# Bidirectional_Amp.net
KiCad netlist of a schematic drawn in EAGLE
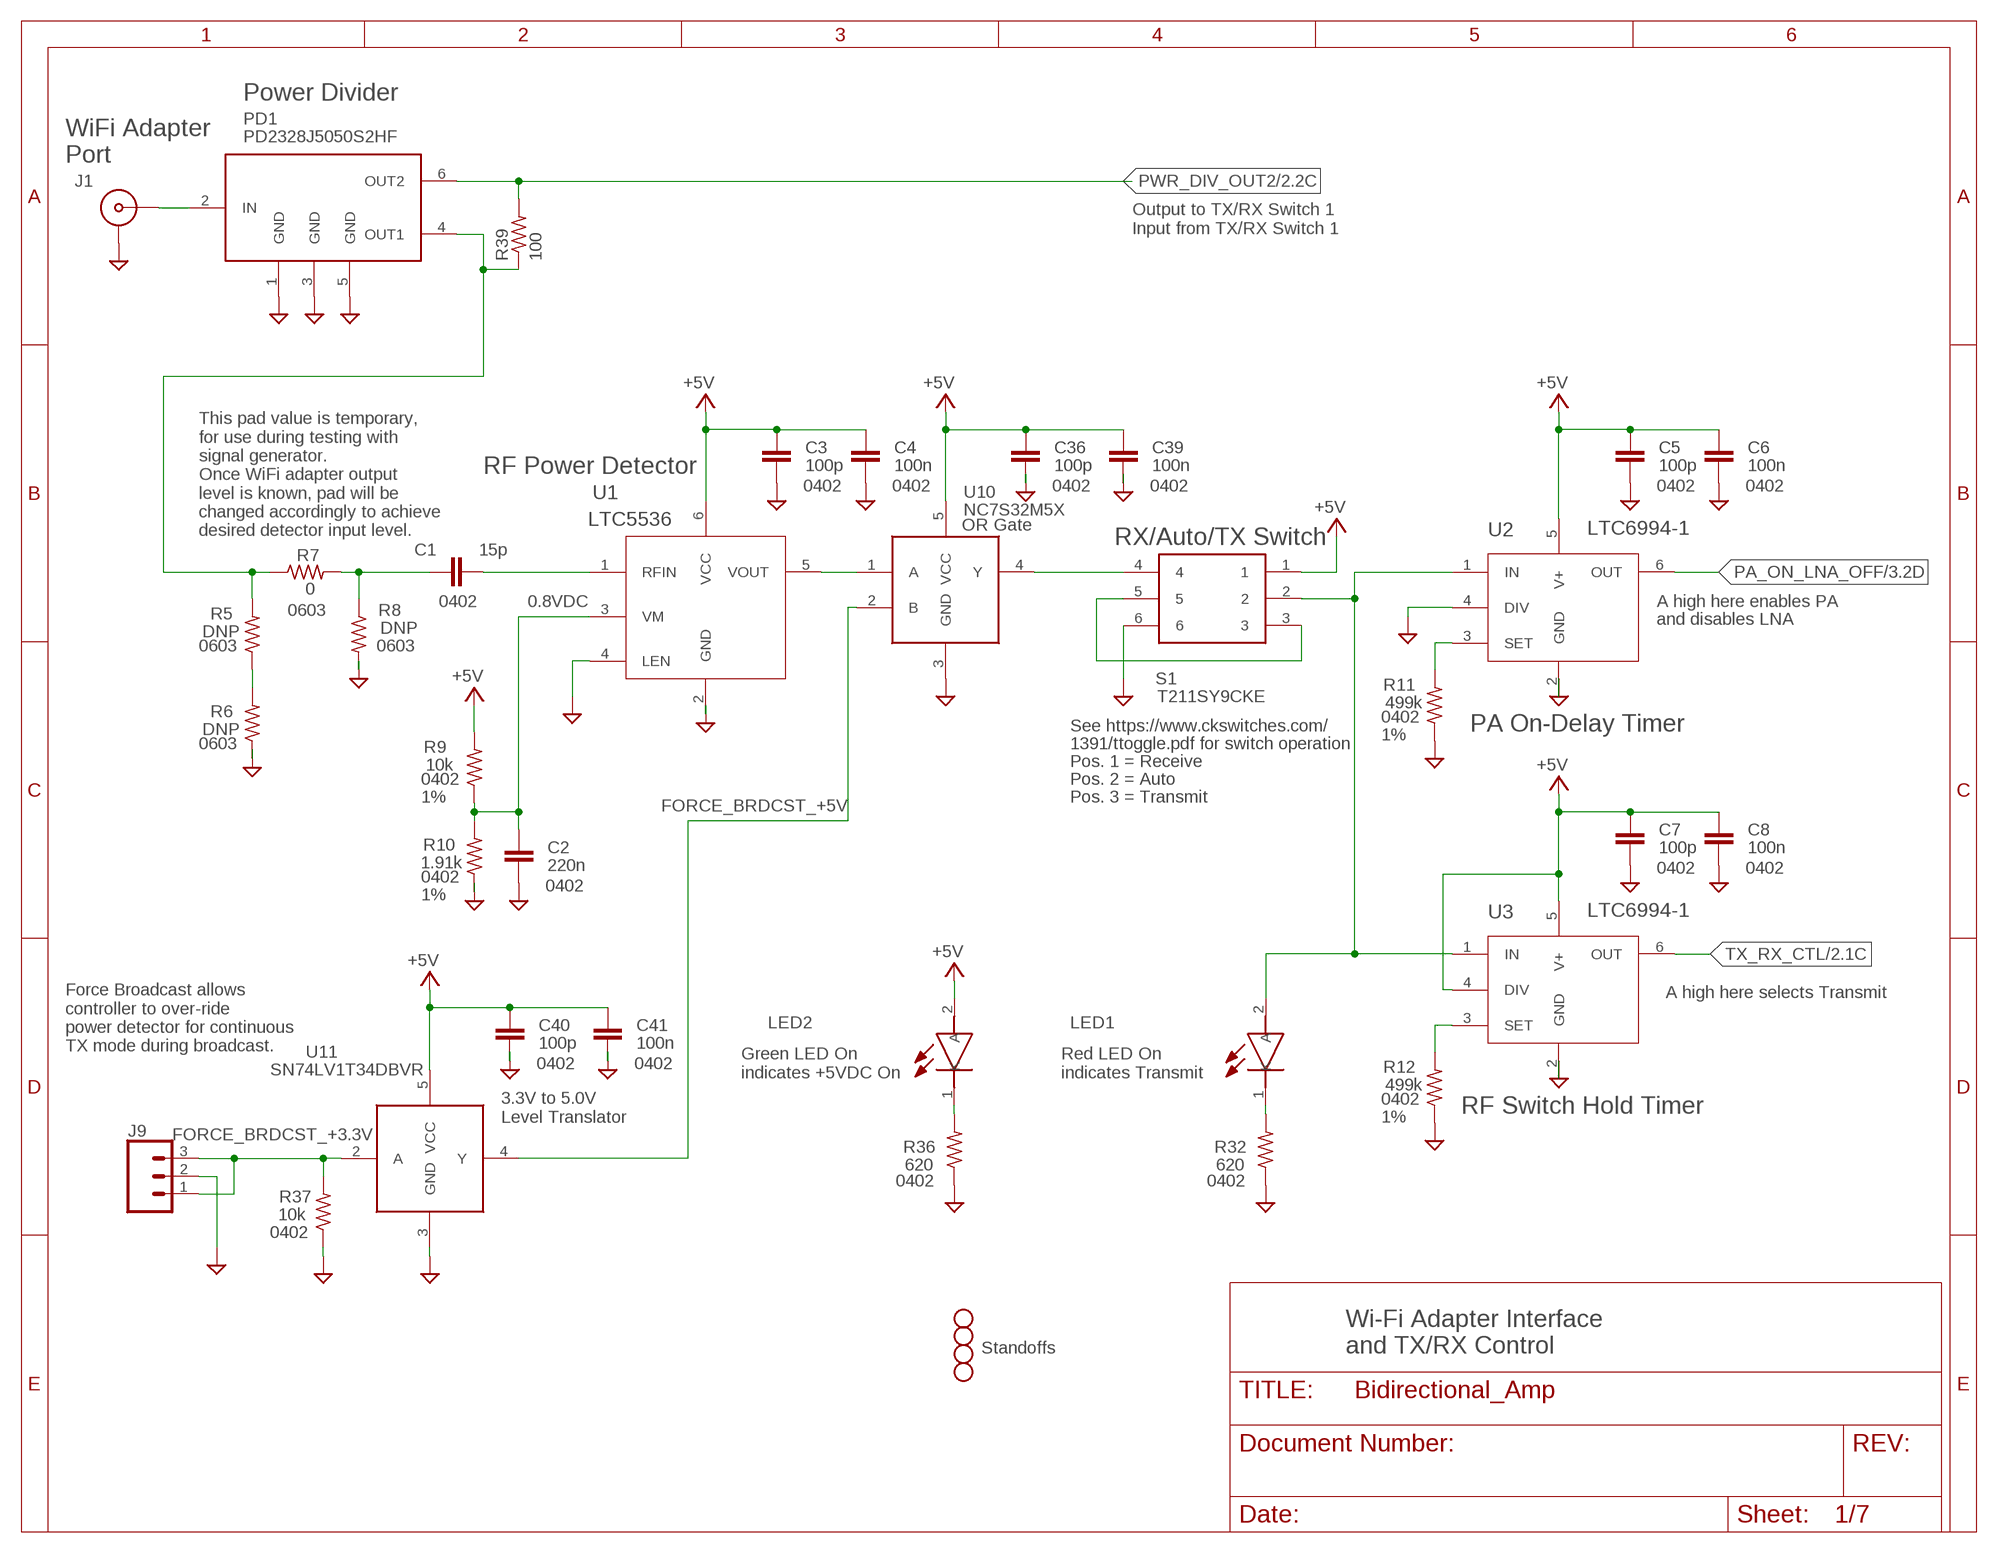
[diagram p0: schematic, sheet 1]
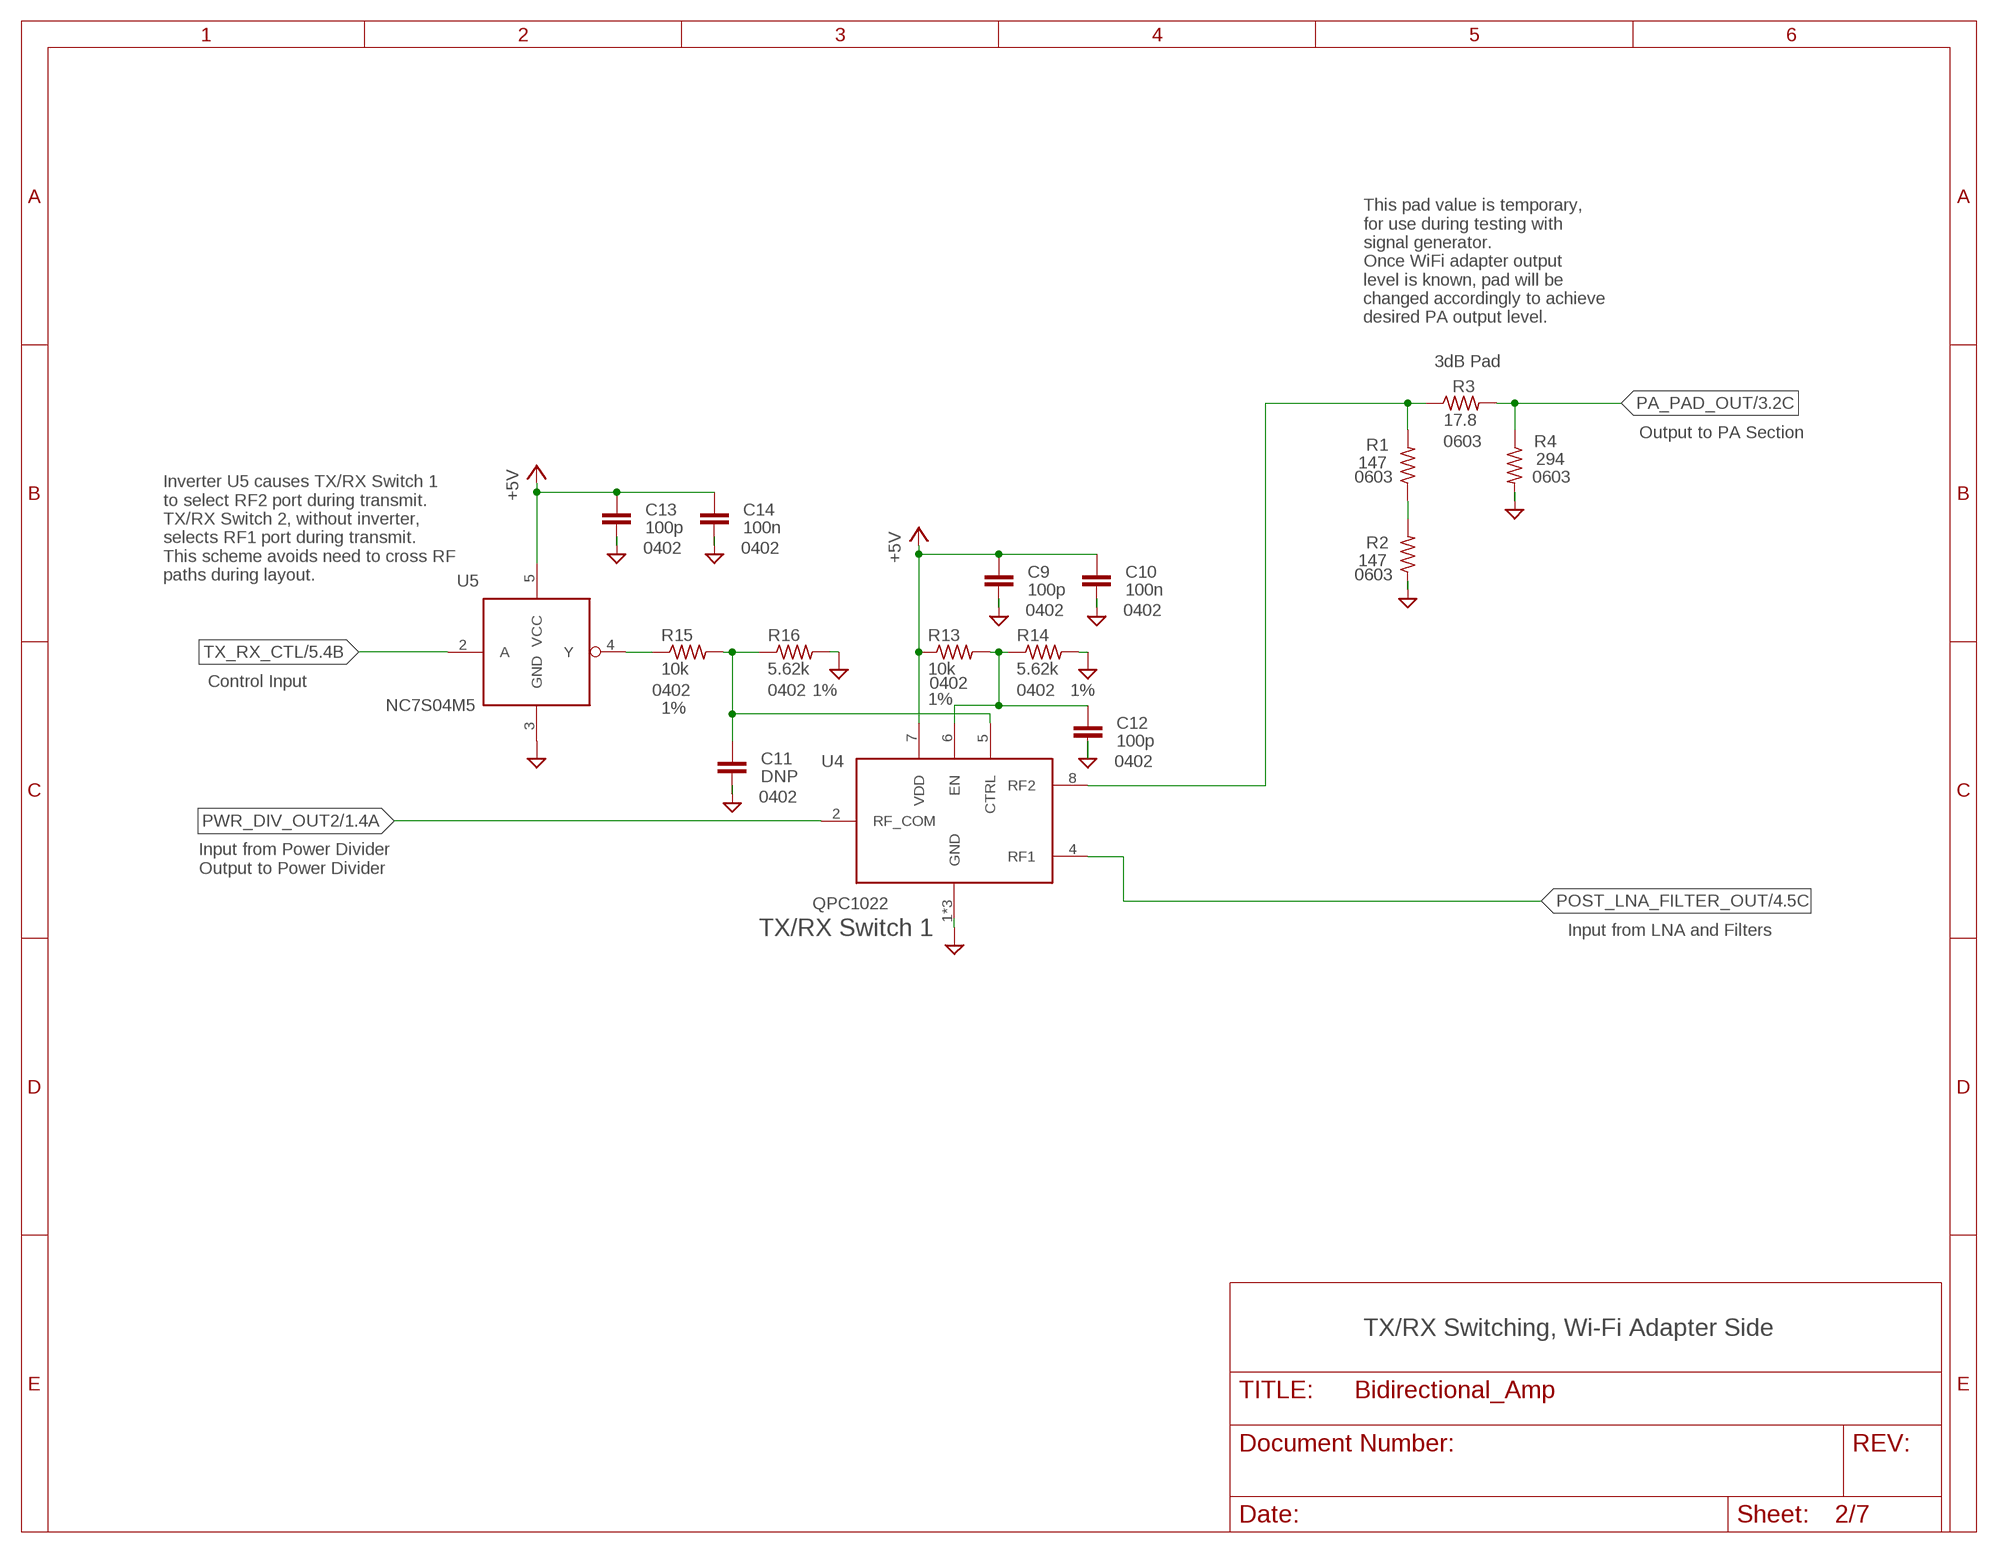
[diagram p1: schematic, sheet 2]
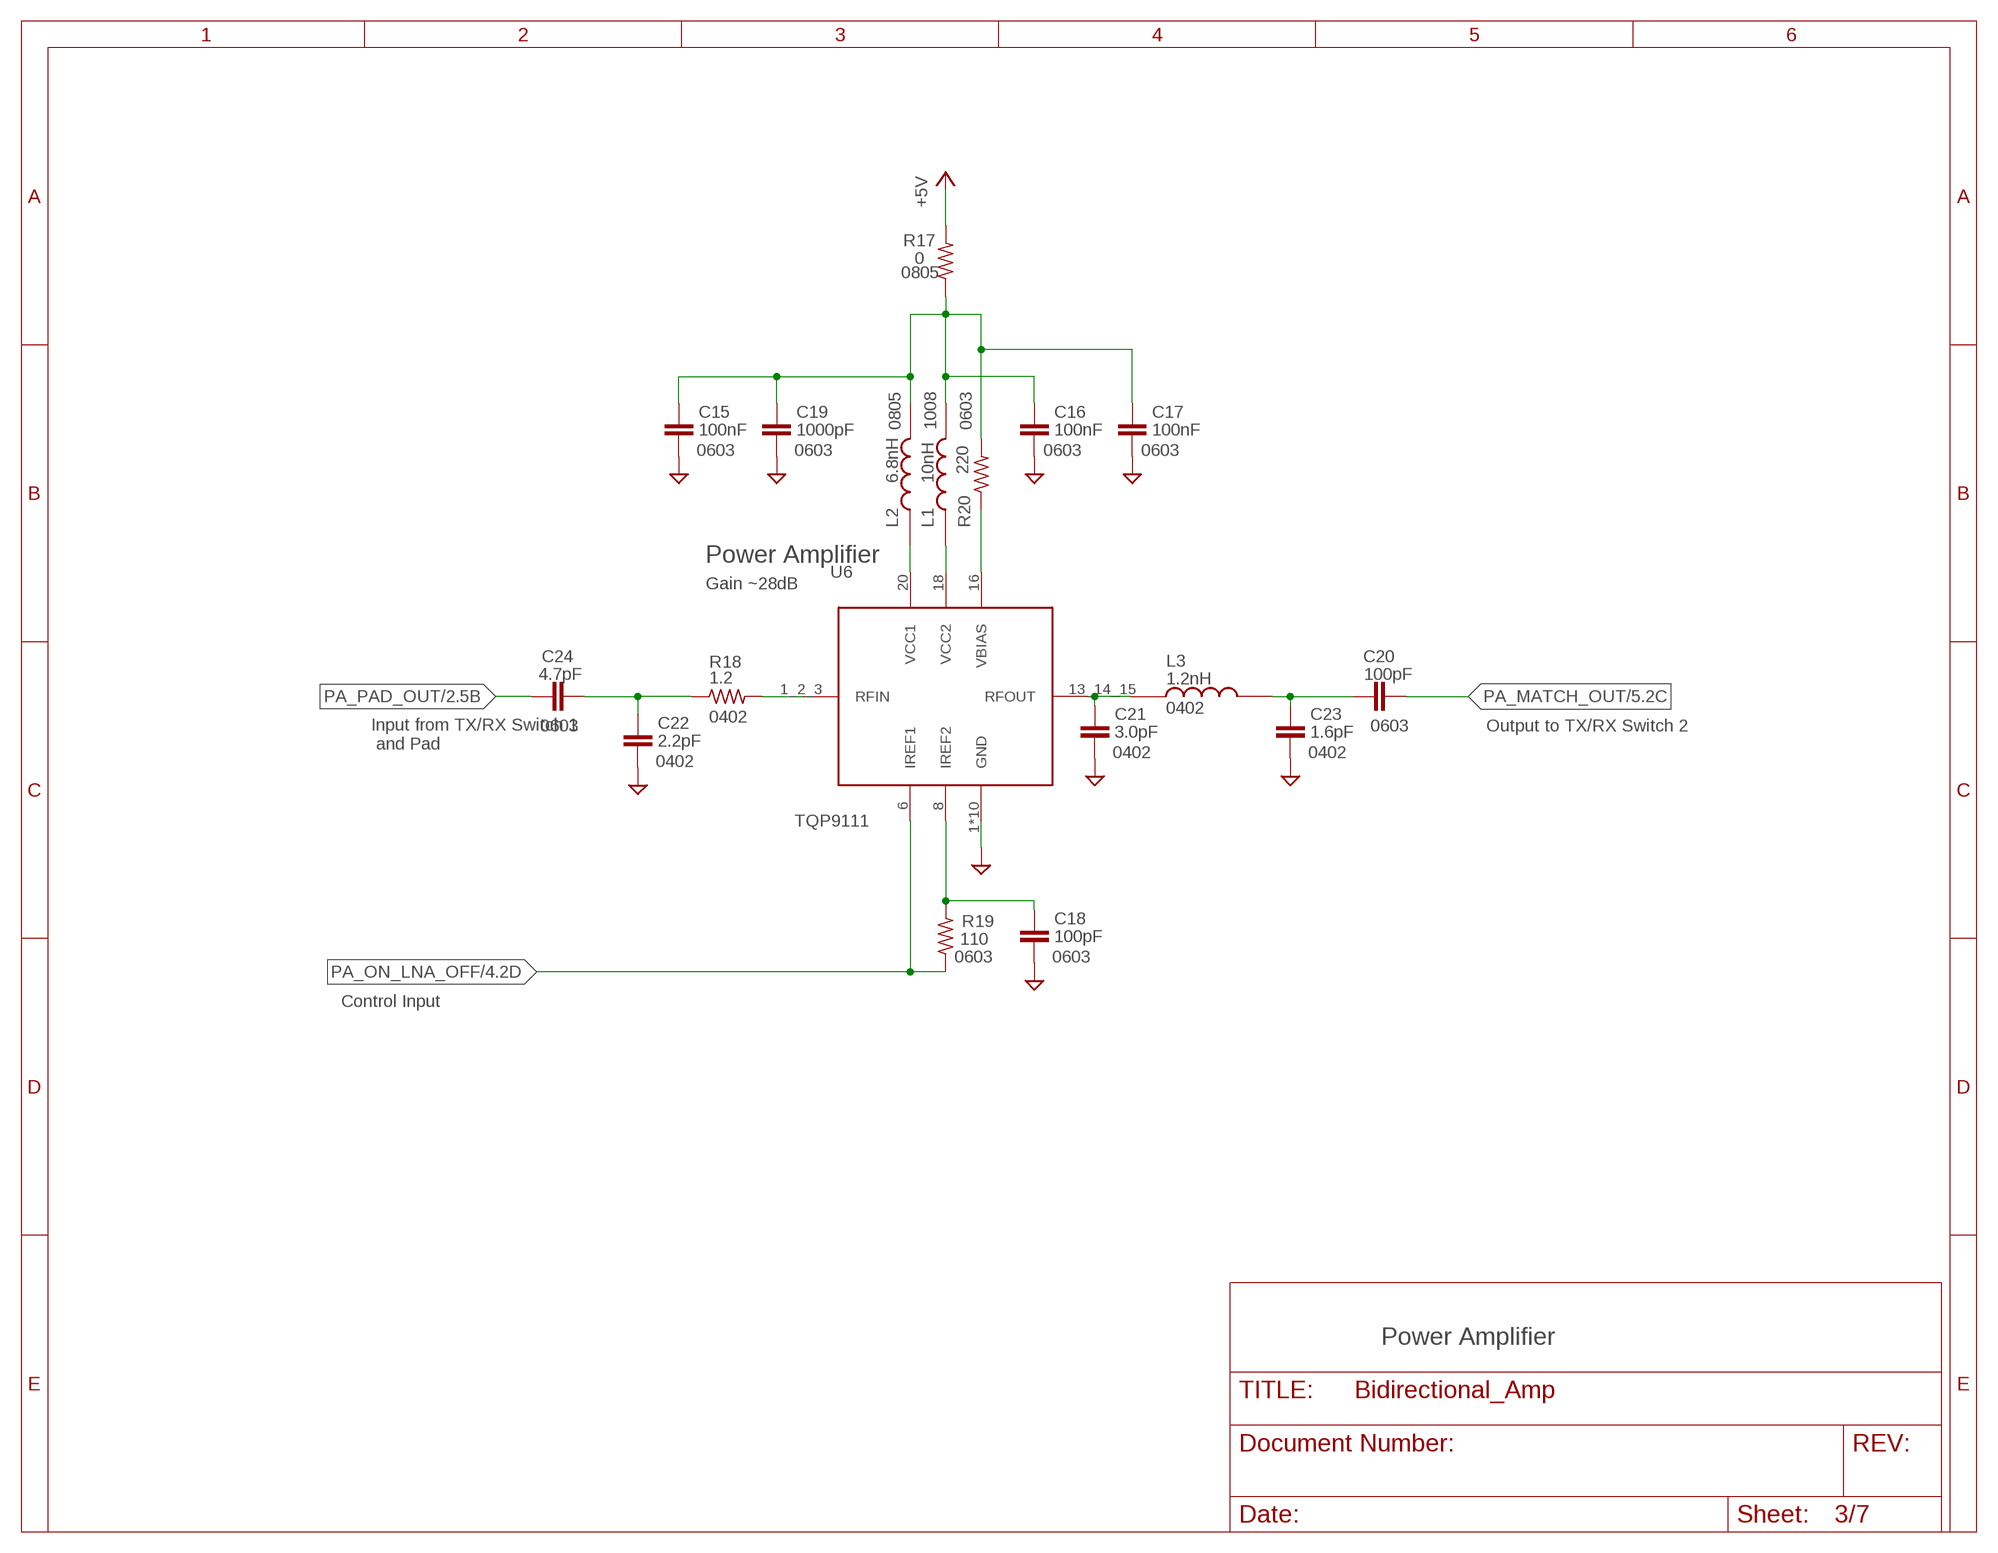
[diagram p2: schematic, sheet 3]
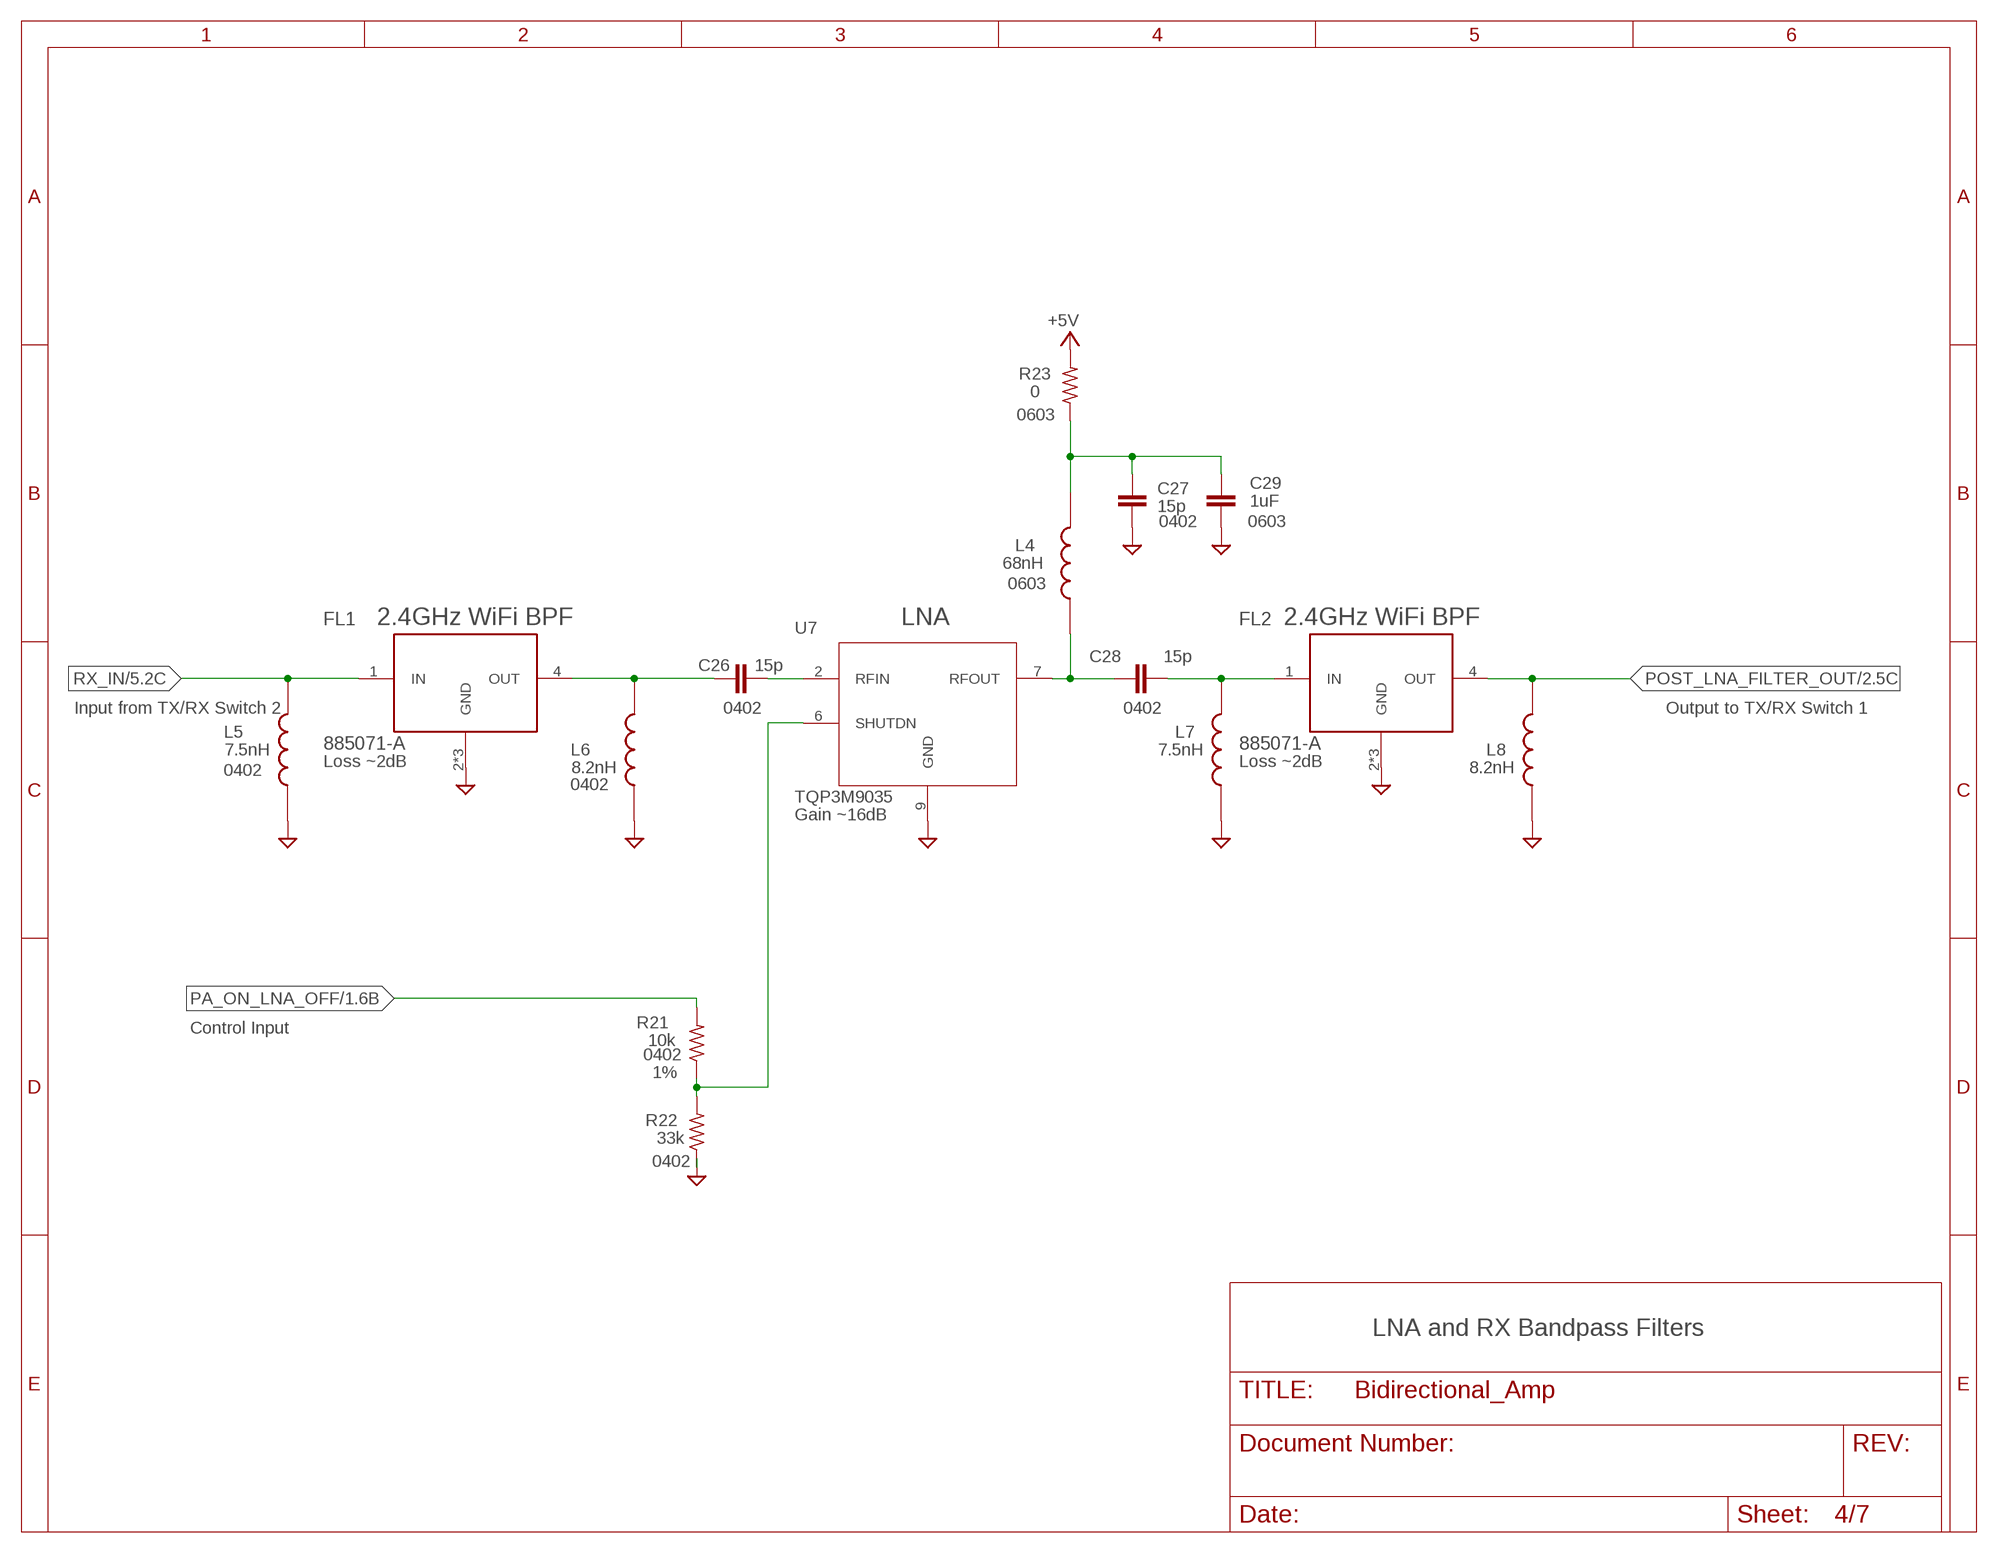
[diagram p3: schematic, sheet 4]
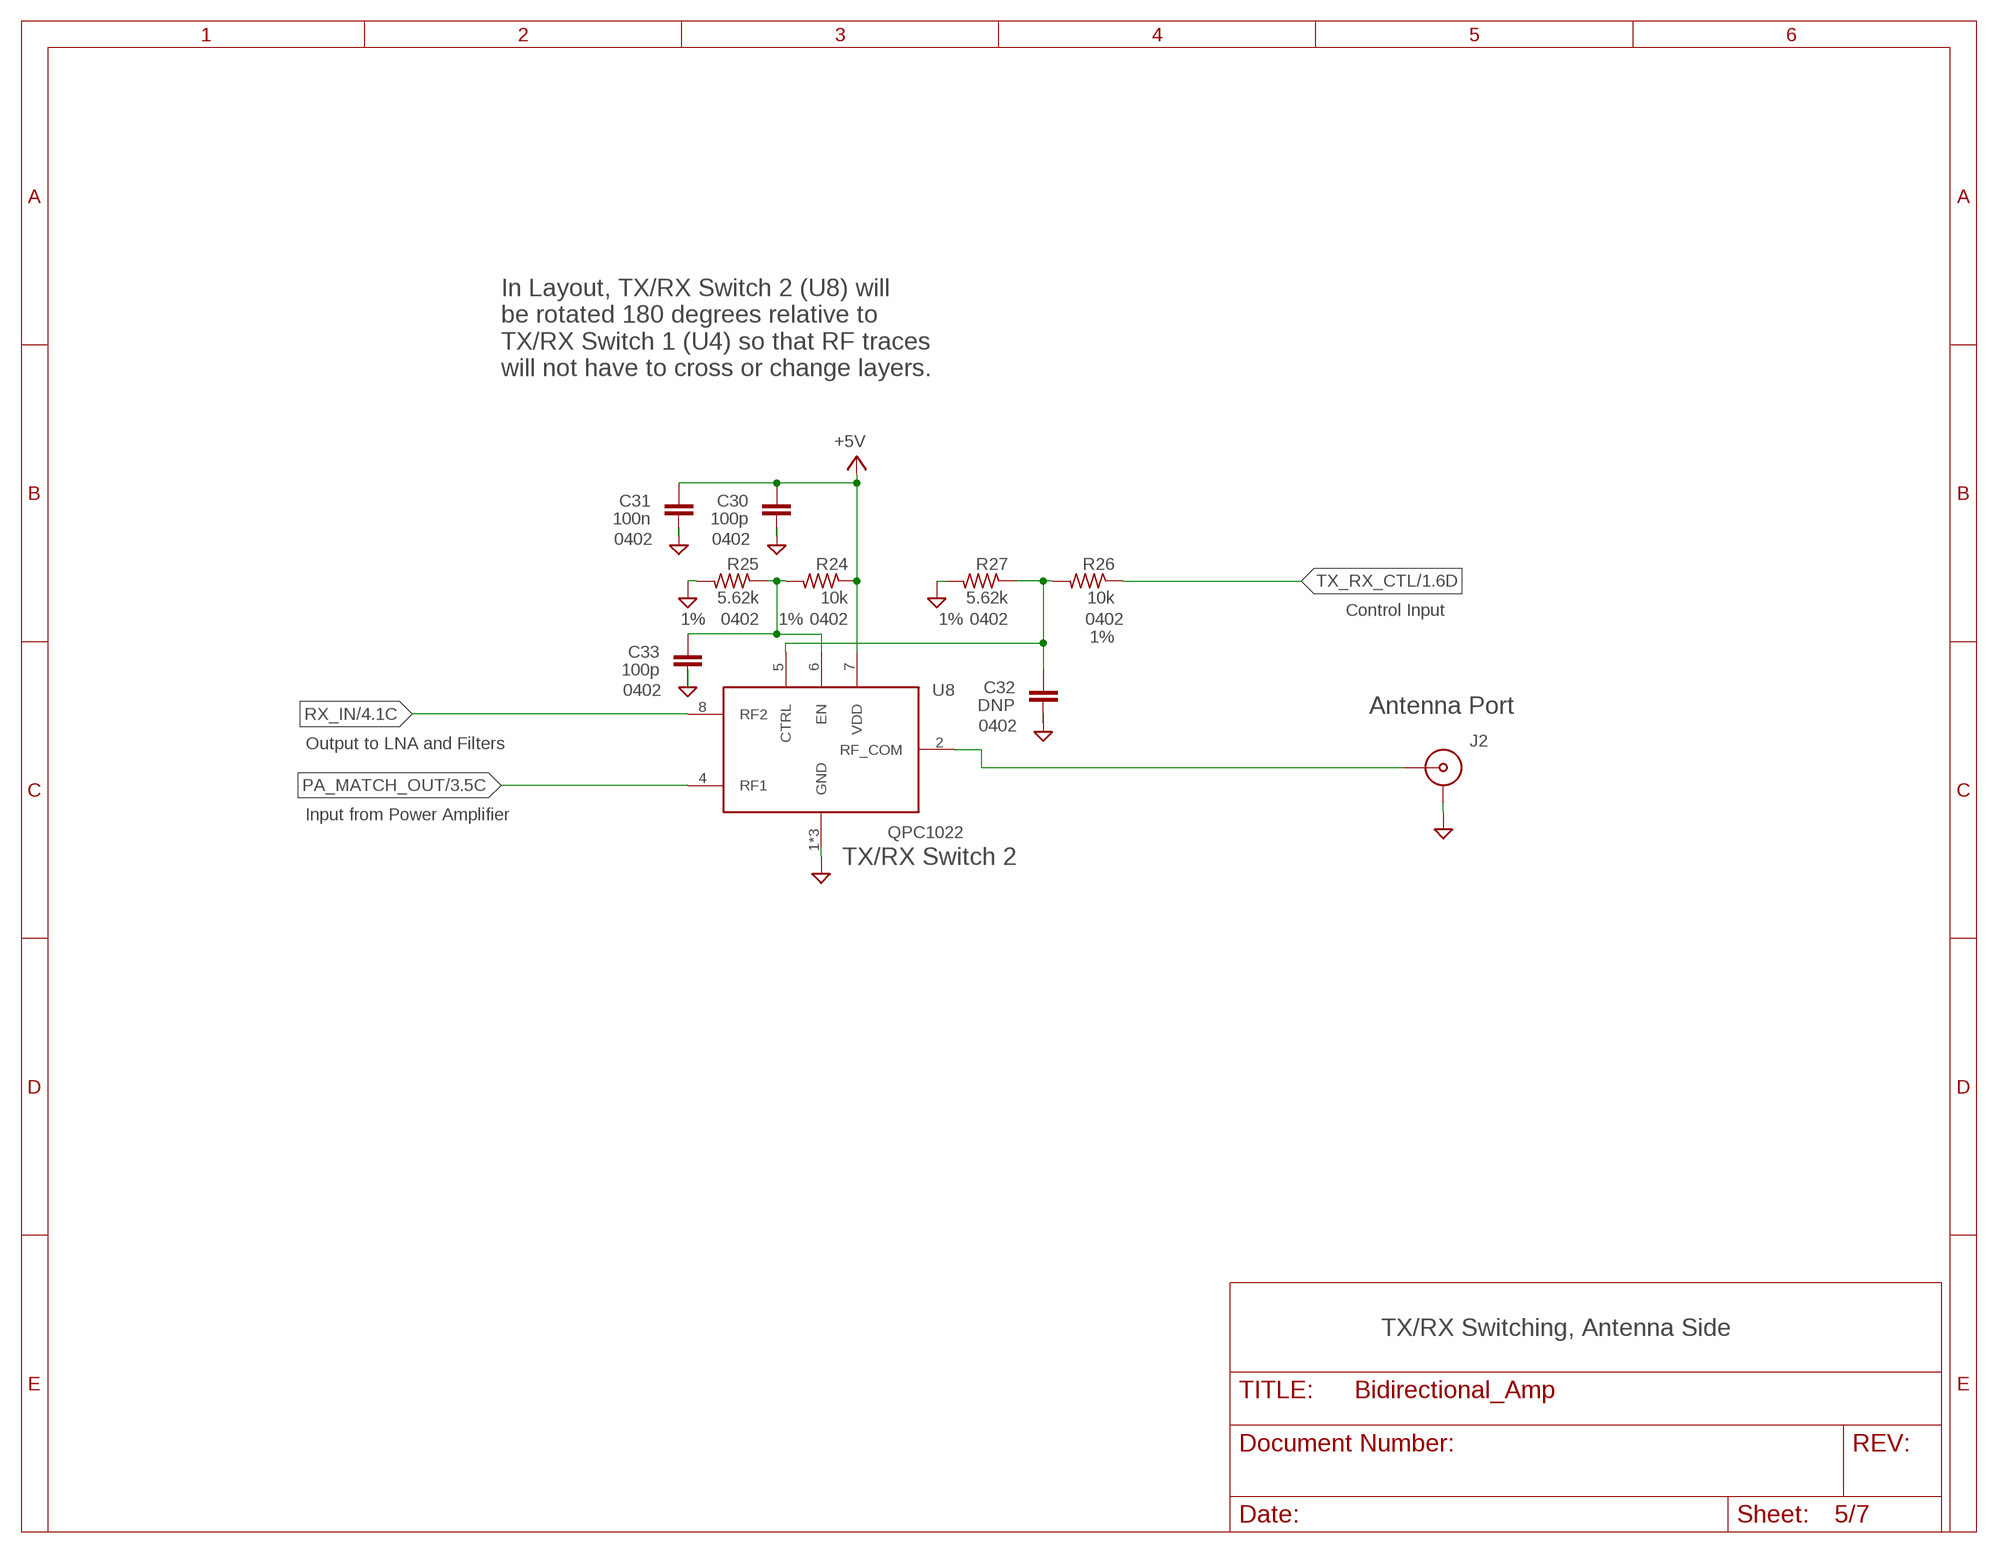
[diagram p4: schematic, sheet 5]
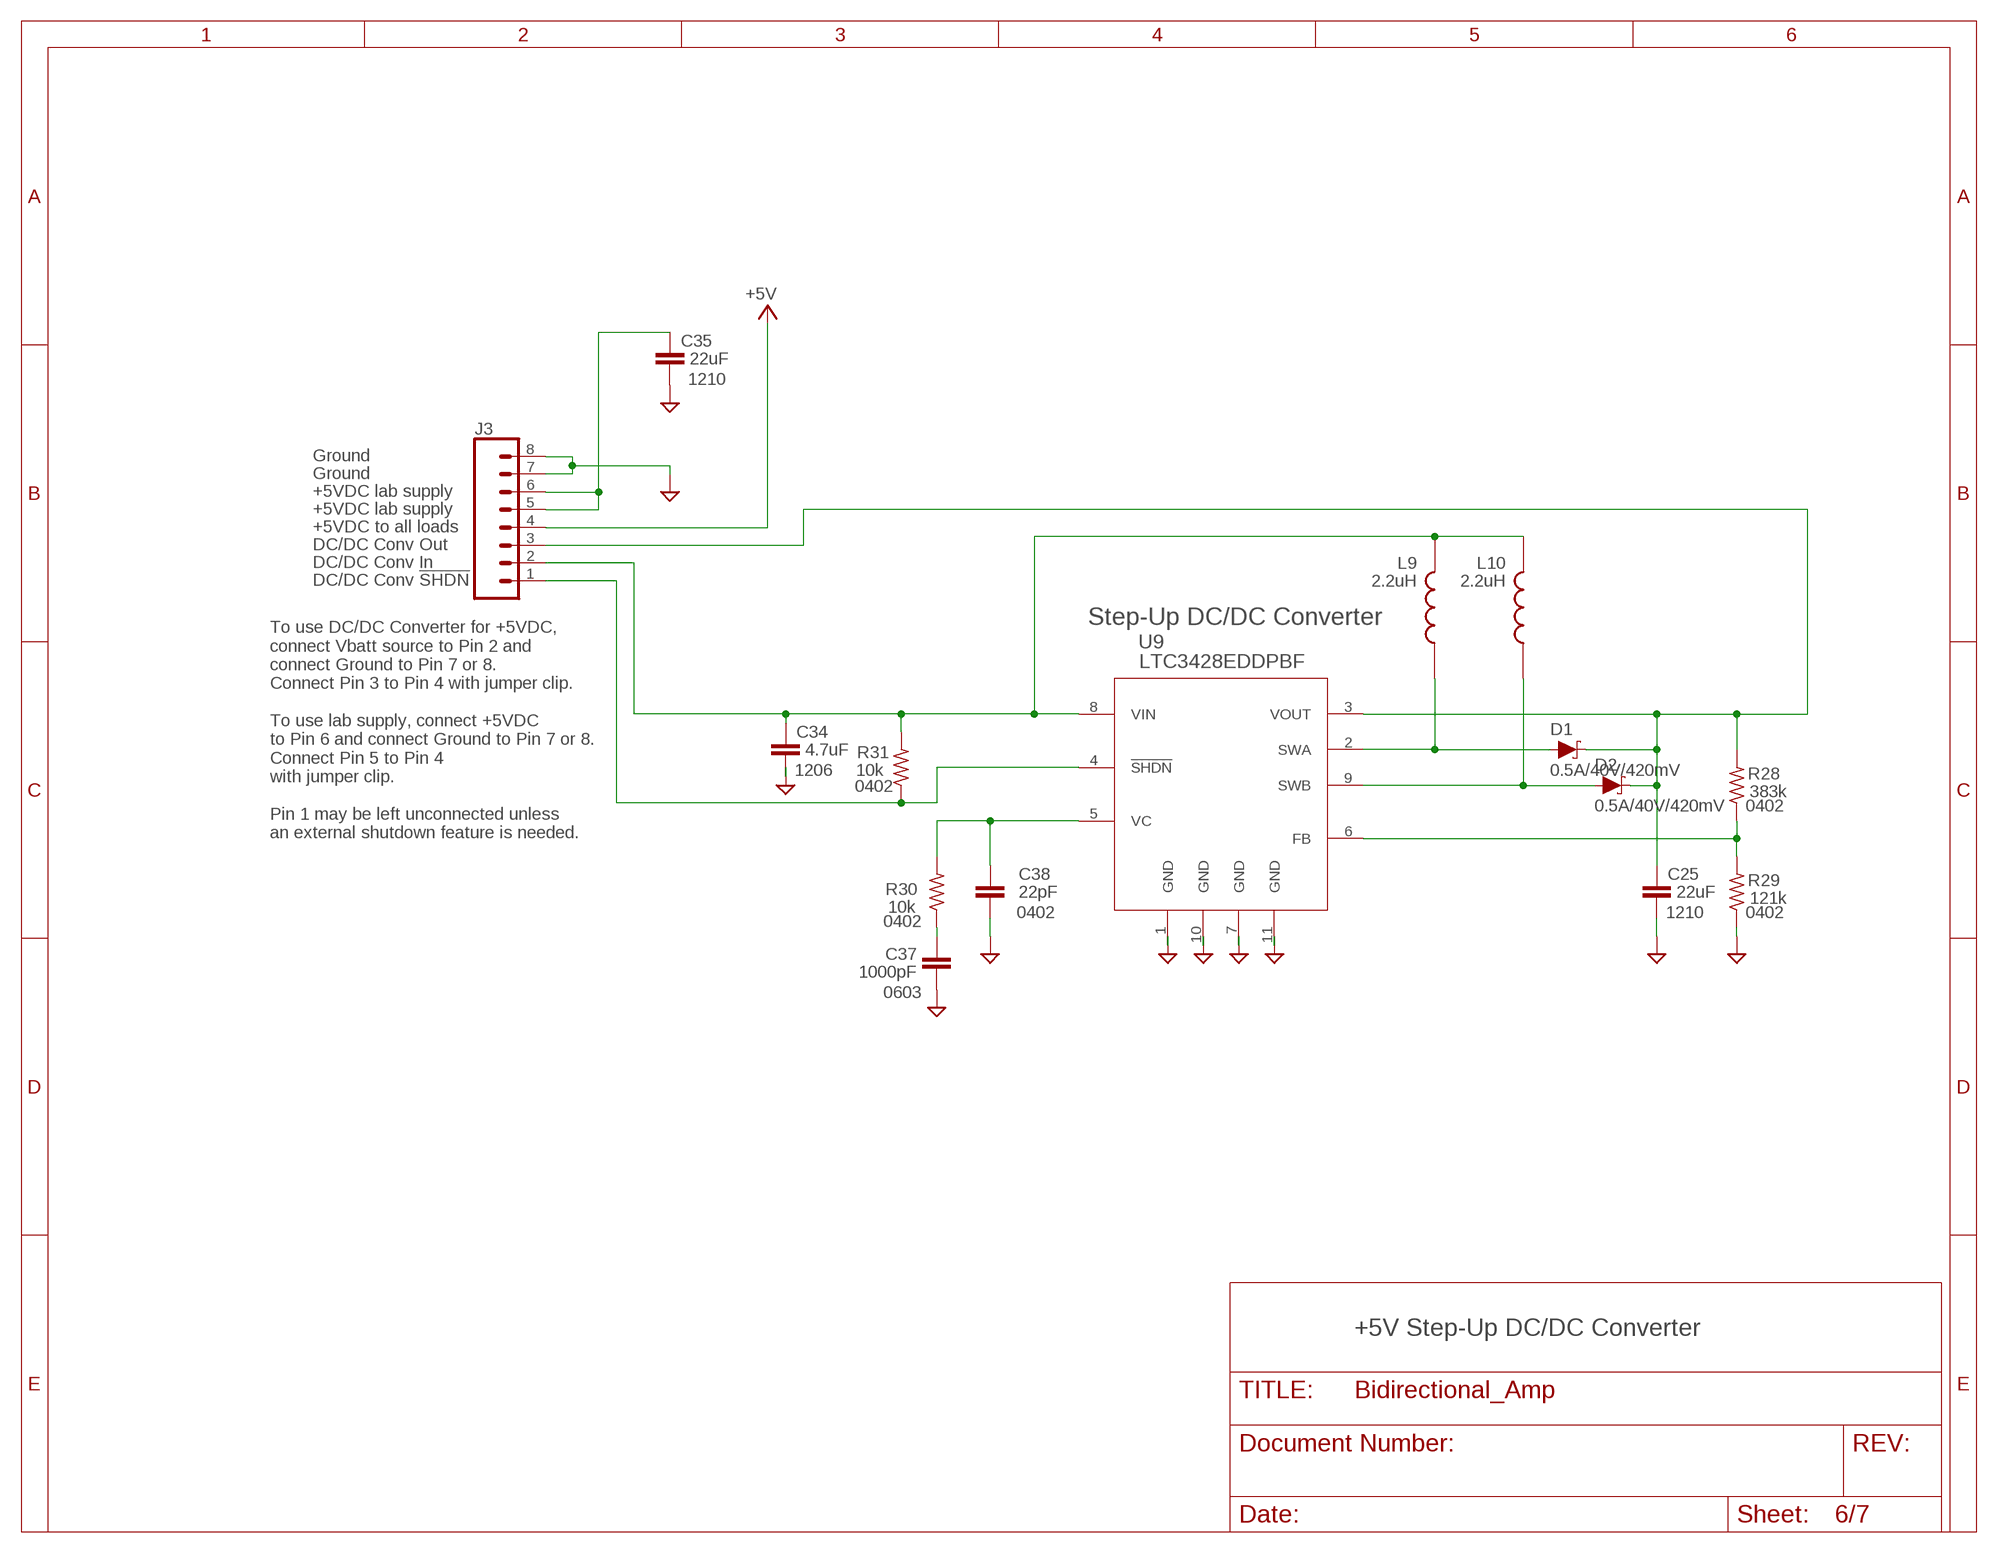
[diagram p5: schematic, sheet 6]
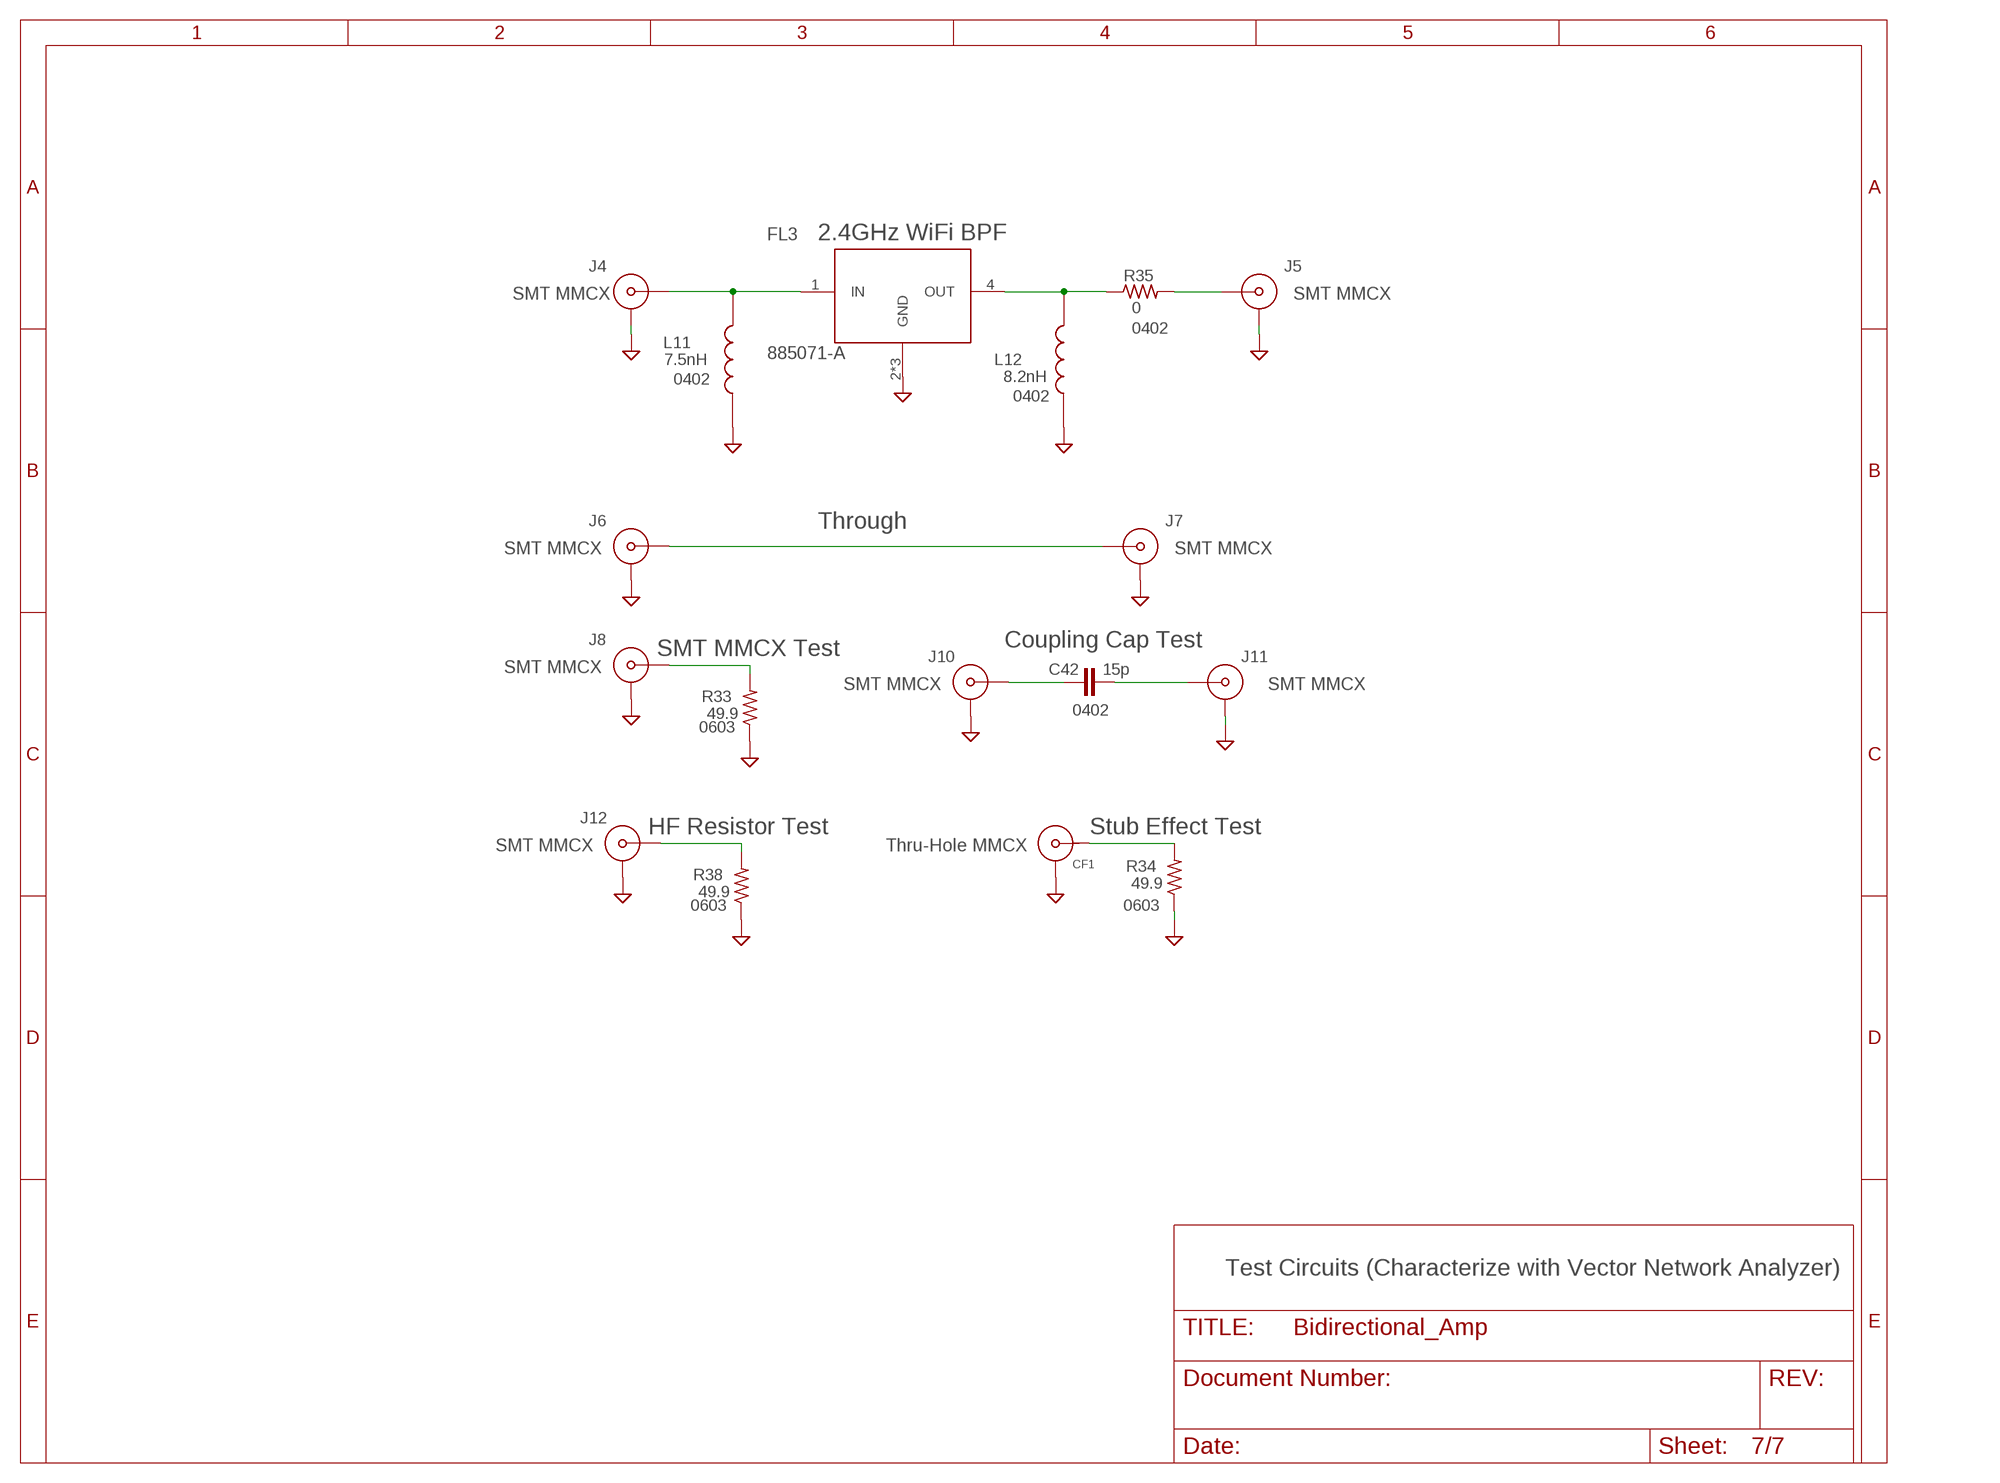
[diagram p6: schematic, sheet 7]

(export (version "E")
  (design (tool "Eeschema 10.0.6"))
  (components
    (comp (ref "C30")
      (value "100p")
      (footprint "eagle-import:.0402-B-NOSILK")
      (fields (field (name "MPN") "GCM1555C1H101JA16D "))
      (libsource (lib "eagle-import") (part "C-EU0402-B-NOSILK"))
    )
    (comp (ref "C31")
      (value "100n")
      (footprint "eagle-import:.0402-B-NOSILK")
      (fields (field (name "MPN") "CGA2B1X7R1C104K050BC"))
      (libsource (lib "eagle-import") (part "C-EU0402-B-NOSILK"))
    )
    (comp (ref "C32")
      (value "DNP")
      (footprint "eagle-import:.0402-B-NOSILK")
      (fields (field (name "MPN") "GCM1555C1H101JA16D "))
      (libsource (lib "eagle-import") (part "C-EU0402-B-NOSILK"))
    )
    (comp (ref "C33")
      (value "100p")
      (footprint "eagle-import:.0402-B-NOSILK")
      (fields (field (name "MPN") "GCM1555C1H101JA16D "))
      (libsource (lib "eagle-import") (part "C-EU0402-B-NOSILK"))
    )
    (comp (ref "J2")
      (value "73415-2061")
      (footprint "eagle-import:73415-2063")
      (fields (field (name "MFR") "Molex") (field (name "MPN") "0734152061"))
      (libsource (lib "eagle-import") (part "73415-2061"))
    )
    (comp (ref "R24")
      (value "10k")
      (footprint "eagle-import:.0402-B-NOSILK")
      (fields (field (name "MPN") "ERJ-2RKF1002X"))
      (libsource (lib "eagle-import") (part "R-US_0402-B-NOSILK"))
    )
    (comp (ref "R25")
      (value "5.62k")
      (footprint "eagle-import:.0402-B-NOSILK")
      (fields (field (name "MPN") "ERJ-2RKF5621X"))
      (libsource (lib "eagle-import") (part "R-US_0402-B-NOSILK"))
    )
    (comp (ref "R26")
      (value "10k")
      (footprint "eagle-import:.0402-B-NOSILK")
      (fields (field (name "MPN") "ERJ-2RKF1002X"))
      (libsource (lib "eagle-import") (part "R-US_0402-B-NOSILK"))
    )
    (comp (ref "R27")
      (value "5.62k")
      (footprint "eagle-import:.0402-B-NOSILK")
      (fields (field (name "MPN") "ERJ-2RKF5621X"))
      (libsource (lib "eagle-import") (part "R-US_0402-B-NOSILK"))
    )
    (comp (ref "U8")
      (value "QPC1022")
      (footprint "eagle-import:QPC1022")
      (fields (field (name "MFR") "Qorvo"))
      (libsource (lib "eagle-import") (part "QPC1022"))
    )
    (comp (ref "C25")
      (value "22uF")
      (footprint "eagle-import:C1210")
      (fields (field (name "MPN") "GCJ32ER71C226KE01L"))
      (libsource (lib "eagle-import") (part "rcl_334_C-EUC1210"))
    )
    (comp (ref "C34")
      (value "4.7uF")
      (footprint "eagle-import:C1206")
      (fields (field (name "MPN") "GCJ31CR71C475KA01L") (field (name "VOLTAGE") "16V"))
      (libsource (lib "eagle-import") (part "rcl_334_C-EUC1206"))
    )
    (comp (ref "C35")
      (value "22uF")
      (footprint "eagle-import:C1210")
      (fields (field (name "MPN") "GCJ32ER71C226KE01L"))
      (libsource (lib "eagle-import") (part "rcl_334_C-EUC1210"))
    )
    (comp (ref "C37")
      (value "1000pF")
      (footprint "eagle-import:C0603")
      (fields (field (name "MPN") "CGA3E2C0G1H102J080AA"))
      (libsource (lib "eagle-import") (part "rcl_334_C-EUC0603"))
    )
    (comp (ref "C38")
      (value "22pF")
      (footprint "eagle-import:.0402-B-NOSILK")
      (fields (field (name "MPN") "GCM1555C1H220JA16J"))
      (libsource (lib "eagle-import") (part "C-EU0402-B-NOSILK"))
    )
    (comp (ref "D1")
      (value "0.5A/40V/420mV")
      (footprint "eagle-import:SOD-323")
      (fields (field (name "MPN") "PMEG1020EJ,115"))
      (libsource (lib "eagle-import") (part "DIODE-SCHOTTKY-PMEG4005EJ"))
    )
    (comp (ref "D2")
      (value "0.5A/40V/420mV")
      (footprint "eagle-import:SOD-323")
      (fields (field (name "MPN") "PMEG1020EJ,115"))
      (libsource (lib "eagle-import") (part "DIODE-SCHOTTKY-PMEG4005EJ"))
    )
    (comp (ref "J3")
      (value "CONN_08LONGPADS")
      (footprint "eagle-import:1X08_LONGPADS")
      (libsource (lib "eagle-import") (part "CONN_08LONGPADS"))
    )
    (comp (ref "L9")
      (value "2.2uH")
      (footprint "eagle-import:XFL4020-222ME")
      (fields (field (name "MFR") "COILCRAFT") (field (name "MPN") "XFL4020-222MEB"))
      (libsource (lib "eagle-import") (part "XFL4020-222MEB"))
    )
    (comp (ref "L10")
      (value "2.2uH")
      (footprint "eagle-import:XFL4020-222ME")
      (fields (field (name "MFR") "COILCRAFT") (field (name "MPN") "XFL4020-222MEB"))
      (libsource (lib "eagle-import") (part "XFL4020-222MEB"))
    )
    (comp (ref "R28")
      (value "383k")
      (footprint "eagle-import:.0402-B-NOSILK")
      (fields (field (name "MPN") "ERJ-2RKF3833X"))
      (libsource (lib "eagle-import") (part "R-US_0402-B-NOSILK"))
    )
    (comp (ref "R29")
      (value "121k")
      (footprint "eagle-import:.0402-B-NOSILK")
      (fields (field (name "MPN") "ERJ-2RKF1213X"))
      (libsource (lib "eagle-import") (part "R-US_0402-B-NOSILK"))
    )
    (comp (ref "R30")
      (value "10k")
      (footprint "eagle-import:.0402-B-NOSILK")
      (fields (field (name "MPN") "ERJ-2RKF1002X"))
      (libsource (lib "eagle-import") (part "R-US_0402-B-NOSILK"))
    )
    (comp (ref "R31")
      (value "10k")
      (footprint "eagle-import:.0402-B-NOSILK")
      (fields (field (name "MPN") "ERJ-2GEJ103X"))
      (libsource (lib "eagle-import") (part "R-US_0402-B-NOSILK"))
    )
    (comp (ref "U9")
      (value "LTC3428EDDPBF")
      (footprint "eagle-import:DFN-10_DD")
      (fields (field (name "MFR") "Linear Technology") (field (name "MPN") "LTC3428EDD#PBF"))
      (libsource (lib "eagle-import") (part "LTC3428EDDPBF"))
    )
    (comp (ref "C1")
      (value "15p")
      (footprint "eagle-import:.0402-B-NOSILK")
      (fields (field (name "MPN") "GJM1555C1H150JB01D "))
      (libsource (lib "eagle-import") (part "C-EU0402-B-NOSILK"))
    )
    (comp (ref "C2")
      (value "220n")
      (footprint "eagle-import:.0402-B-NOSILK")
      (fields (field (name "MPN") "C1005X7R1C224K050BE "))
      (libsource (lib "eagle-import") (part "C-EU0402-B-NOSILK"))
    )
    (comp (ref "C3")
      (value "100p")
      (footprint "eagle-import:.0402-B-NOSILK")
      (fields (field (name "MPN") "GCM1555C1H101JA16D "))
      (libsource (lib "eagle-import") (part "C-EU0402-B-NOSILK"))
    )
    (comp (ref "C4")
      (value "100n")
      (footprint "eagle-import:.0402-B-NOSILK")
      (fields (field (name "MPN") "CGA2B1X7R1C104K050BC"))
      (libsource (lib "eagle-import") (part "C-EU0402-B-NOSILK"))
    )
    (comp (ref "C5")
      (value "100p")
      (footprint "eagle-import:.0402-B-NOSILK")
      (fields (field (name "MPN") "GCM1555C1H101JA16D "))
      (libsource (lib "eagle-import") (part "C-EU0402-B-NOSILK"))
    )
    (comp (ref "C6")
      (value "100n")
      (footprint "eagle-import:.0402-B-NOSILK")
      (fields (field (name "MPN") "CGA2B1X7R1C104K050BC"))
      (libsource (lib "eagle-import") (part "C-EU0402-B-NOSILK"))
    )
    (comp (ref "C7")
      (value "100p")
      (footprint "eagle-import:.0402-B-NOSILK")
      (fields (field (name "MPN") "GCM1555C1H101JA16D "))
      (libsource (lib "eagle-import") (part "C-EU0402-B-NOSILK"))
    )
    (comp (ref "C8")
      (value "100n")
      (footprint "eagle-import:.0402-B-NOSILK")
      (fields (field (name "MPN") "CGA2B1X7R1C104K050BC"))
      (libsource (lib "eagle-import") (part "C-EU0402-B-NOSILK"))
    )
    (comp (ref "C36")
      (value "100p")
      (footprint "eagle-import:.0402-B-NOSILK")
      (fields (field (name "MPN") "GCM1555C1H101JA16D "))
      (libsource (lib "eagle-import") (part "C-EU0402-B-NOSILK"))
    )
    (comp (ref "C39")
      (value "100n")
      (footprint "eagle-import:.0402-B-NOSILK")
      (fields (field (name "MPN") "CGA2B1X7R1C104K050BC"))
      (libsource (lib "eagle-import") (part "C-EU0402-B-NOSILK"))
    )
    (comp (ref "C40")
      (value "100p")
      (footprint "eagle-import:.0402-B-NOSILK")
      (fields (field (name "MPN") "GCM1555C1H101JA16D "))
      (libsource (lib "eagle-import") (part "C-EU0402-B-NOSILK"))
    )
    (comp (ref "C41")
      (value "100n")
      (footprint "eagle-import:.0402-B-NOSILK")
      (fields (field (name "MPN") "CGA2B1X7R1C104K050BC"))
      (libsource (lib "eagle-import") (part "C-EU0402-B-NOSILK"))
    )
    (comp (ref "H1")
      (value "STAND-OFFTIGHT")
      (footprint "eagle-import:STAND-OFF-TIGHT")
      (libsource (lib "eagle-import") (part "STAND-OFFTIGHT"))
    )
    (comp (ref "H2")
      (value "STAND-OFFTIGHT")
      (footprint "eagle-import:STAND-OFF-TIGHT")
      (libsource (lib "eagle-import") (part "STAND-OFFTIGHT"))
    )
    (comp (ref "H3")
      (value "STAND-OFFTIGHT")
      (footprint "eagle-import:STAND-OFF-TIGHT")
      (libsource (lib "eagle-import") (part "STAND-OFFTIGHT"))
    )
    (comp (ref "H4")
      (value "STAND-OFFTIGHT")
      (footprint "eagle-import:STAND-OFF-TIGHT")
      (libsource (lib "eagle-import") (part "STAND-OFFTIGHT"))
    )
    (comp (ref "J1")
      (value "73415-2061")
      (footprint "eagle-import:73415-2063")
      (fields
        (field (name "MFR") "Molex")
        (field (name "MPN") "0734152061")
        (field (name "MPN_1") "0734152061")
      )
      (libsource (lib "eagle-import") (part "73415-2061"))
    )
    (comp (ref "J9")
      (value "CONN_03LONGPADS")
      (footprint "eagle-import:1X03_LONGPADS")
      (libsource (lib "eagle-import") (part "CONN_03LONGPADS"))
    )
    (comp (ref "LED1")
      (value "LTST-C193KRKT-5A")
      (footprint "eagle-import:LEDC1607X80N")
      (fields (field (name "MFR") "Lite-On"))
      (libsource (lib "eagle-import") (part "LTST-C193KRKT-5A"))
    )
    (comp (ref "LED2")
      (value "LTST-C193KGKT-5A")
      (footprint "eagle-import:LEDC1607X80N")
      (fields (field (name "MFR") "Lite-On"))
      (libsource (lib "eagle-import") (part "LTST-C193KGKT-5A"))
    )
    (comp (ref "PD1")
      (value "PD2328J5050S2HF")
      (footprint "eagle-import:PSON65P204X129X58-6N")
      (fields (field (name "MFR") "ANAREN"))
      (libsource (lib "eagle-import") (part "PD2328J5050S2HF"))
    )
    (comp (ref "R5")
      (value "DNP")
      (footprint "eagle-import:R0603")
      (libsource (lib "eagle-import") (part "rcl_334_R-US_R0603"))
    )
    (comp (ref "R6")
      (value "DNP")
      (footprint "eagle-import:R0603")
      (libsource (lib "eagle-import") (part "rcl_334_R-US_R0603"))
    )
    (comp (ref "R7")
      (value "0")
      (footprint "eagle-import:R0603")
      (fields (field (name "MPN") "ERJ-3GEY0R00V"))
      (libsource (lib "eagle-import") (part "rcl_334_R-US_R0603"))
    )
    (comp (ref "R8")
      (value "DNP")
      (footprint "eagle-import:R0603")
      (libsource (lib "eagle-import") (part "rcl_334_R-US_R0603"))
    )
    (comp (ref "R9")
      (value "10k")
      (footprint "eagle-import:.0402-B-NOSILK")
      (fields (field (name "MPN") "ERJ-2RKF1002X"))
      (libsource (lib "eagle-import") (part "R-US_0402-B-NOSILK"))
    )
    (comp (ref "R10")
      (value "1.91k")
      (footprint "eagle-import:.0402-B-NOSILK")
      (fields (field (name "MPN") "ERJ-2RKF1911X"))
      (libsource (lib "eagle-import") (part "R-US_0402-B-NOSILK"))
    )
    (comp (ref "R11")
      (value "499k")
      (footprint "eagle-import:.0402-B-NOSILK")
      (fields (field (name "MPN") "ERJ-2RKF4993X"))
      (libsource (lib "eagle-import") (part "R-US_0402-B-NOSILK"))
    )
    (comp (ref "R12")
      (value "499k")
      (footprint "eagle-import:.0402-B-NOSILK")
      (fields (field (name "MPN") "ERJ-2RKF4993X"))
      (libsource (lib "eagle-import") (part "R-US_0402-B-NOSILK"))
    )
    (comp (ref "R32")
      (value "620")
      (footprint "eagle-import:.0402-B-NOSILK")
      (fields (field (name "MPN") "ERJ-2GEJ621X"))
      (libsource (lib "eagle-import") (part "R-US_0402-B-NOSILK"))
    )
    (comp (ref "R36")
      (value "620")
      (footprint "eagle-import:.0402-B-NOSILK")
      (fields (field (name "MPN") "ERJ-2GEJ621X"))
      (libsource (lib "eagle-import") (part "R-US_0402-B-NOSILK"))
    )
    (comp (ref "R37")
      (value "10k")
      (footprint "eagle-import:.0402-B-NOSILK")
      (fields (field (name "MPN") "ERJ-2GEJ103X"))
      (libsource (lib "eagle-import") (part "R-US_0402-B-NOSILK"))
    )
    (comp (ref "R39")
      (value "100")
      (footprint "eagle-import:.0603-C-NOSILK")
      (fields (field (name "PARTNUM") "ERJ-3EKF1000V"))
      (libsource (lib "eagle-import") (part "R-US_0603-C-NOSILK"))
    )
    (comp (ref "S1")
      (value "T211SY9CKE")
      (footprint "eagle-import:T201MH9V3BE")
      (fields (field (name "MFR") "C & K COMPONENTS") (field (name "MPN") "T211SY9CQE"))
      (libsource (lib "eagle-import") (part "T201MH9V3BE"))
    )
    (comp (ref "U1")
      (value "LTC5536")
      (footprint "eagle-import:TSOT-23_S6")
      (fields (field (name "MFR") "Linear Technology"))
      (libsource (lib "eagle-import") (part "LTC5536ES6TRMPBF"))
    )
    (comp (ref "U2")
      (value "LTC6994-1")
      (footprint "eagle-import:TSOT-23_S6")
      (fields (field (name "MFR") "Linear Technology"))
      (libsource (lib "eagle-import") (part "LTC6994CS6-1PBF"))
    )
    (comp (ref "U3")
      (value "LTC6994-1")
      (footprint "eagle-import:TSOT-23_S6")
      (fields (field (name "MFR") "Linear Technology"))
      (libsource (lib "eagle-import") (part "LTC6994CS6-1PBF"))
    )
    (comp (ref "U10")
      (value "NC7S32M5X")
      (footprint "eagle-import:SOT95P280X145-5N")
      (fields (field (name "MFR") "ON Semiconductor"))
      (libsource (lib "eagle-import") (part "NC7S32M5X"))
    )
    (comp (ref "U11")
      (value "SN74LV1T34DBVR")
      (footprint "eagle-import:SOT95P280X145-5N")
      (fields (field (name "MFR") "Texas Instruments"))
      (libsource (lib "eagle-import") (part "SN74LV1T34DBVR"))
    )
    (comp (ref "C26")
      (value "15p")
      (footprint "eagle-import:C0402")
      (fields (field (name "MPN") "GJM1555C1H150JB01D "))
      (libsource (lib "eagle-import") (part "rcl_334_C-EUC0402"))
    )
    (comp (ref "C27")
      (value "15p")
      (footprint "eagle-import:.0402-B-NOSILK")
      (fields (field (name "MPN") "GJM1555C1H150JB01D "))
      (libsource (lib "eagle-import") (part "C-EU0402-B-NOSILK"))
    )
    (comp (ref "C28")
      (value "15p")
      (footprint "eagle-import:C0402")
      (fields (field (name "MPN") "GJM1555C1H150JB01D "))
      (libsource (lib "eagle-import") (part "rcl_334_C-EUC0402"))
    )
    (comp (ref "C29")
      (value "1uF")
      (footprint "eagle-import:C0603")
      (fields (field (name "MPN") "C0603X105M4RACAUTO "))
      (libsource (lib "eagle-import") (part "rcl_334_C-EUC0603"))
    )
    (comp (ref "FL1")
      (value "885071-A")
      (footprint "eagle-import:FIL_B39162B9417K610")
      (fields (field (name "MFR") "Qorvo") (field (name "MPN") "885071-A"))
      (libsource (lib "eagle-import") (part "885071-A"))
    )
    (comp (ref "FL2")
      (value "885071-A")
      (footprint "eagle-import:FIL_B39162B9417K610")
      (fields (field (name "MFR") "Qorvo") (field (name "MPN") "885071-A"))
      (libsource (lib "eagle-import") (part "885071-A"))
    )
    (comp (ref "L4")
      (value "68nH")
      (footprint "eagle-import:0603CS-68NXJLW")
      (fields (field (name "MFR") "COILCRAFT") (field (name "MPN") "0603CS-68NXJLW"))
      (libsource (lib "eagle-import") (part "0603CS-68NXJLW"))
    )
    (comp (ref "L5")
      (value "7.5nH")
      (footprint "eagle-import:0402CS1N2XJLW")
      (fields
        (field (name "MFR") "COILCRAFT")
        (field (name "MPN") "0402CS-1N2XJLW")
        (field (name "MPN_1") "0402CS-7N5XGLU")
      )
      (libsource (lib "eagle-import") (part "0402CS-1N2XJLW"))
    )
    (comp (ref "L6")
      (value "8.2nH")
      (footprint "eagle-import:0402CS1N2XJLW")
      (fields
        (field (name "MFR") "COILCRAFT")
        (field (name "MPN") "0402CS-1N2XJLW")
        (field (name "MPN_1") "0402CS-8N2XGLU")
      )
      (libsource (lib "eagle-import") (part "0402CS-1N2XJLW"))
    )
    (comp (ref "L7")
      (value "7.5nH")
      (footprint "eagle-import:0402CS1N2XJLW")
      (fields
        (field (name "MFR") "COILCRAFT")
        (field (name "MPN") "0402CS-1N2XJLW")
        (field (name "MPN_1") "0402CS-7N5XGLU")
      )
      (libsource (lib "eagle-import") (part "0402CS-1N2XJLW"))
    )
    (comp (ref "L8")
      (value "8.2nH")
      (footprint "eagle-import:0402CS1N2XJLW")
      (fields
        (field (name "MFR") "COILCRAFT")
        (field (name "MPN") "0402CS-1N2XJLW")
        (field (name "MPN_1") "0402CS-8N2XGLU")
      )
      (libsource (lib "eagle-import") (part "0402CS-1N2XJLW"))
    )
    (comp (ref "R21")
      (value "10k")
      (footprint "eagle-import:.0402-B-NOSILK")
      (fields (field (name "MPN") "ERJ-2RKF1002X"))
      (libsource (lib "eagle-import") (part "R-US_0402-B-NOSILK"))
    )
    (comp (ref "R22")
      (value "33k")
      (footprint "eagle-import:.0402-B-NOSILK")
      (fields (field (name "MPN") "ERJ-2GEJ333X"))
      (libsource (lib "eagle-import") (part "R-US_0402-B-NOSILK"))
    )
    (comp (ref "R23")
      (value "0")
      (footprint "eagle-import:R0603")
      (fields (field (name "MPN") "ERJ-3GEY0R00V"))
      (libsource (lib "eagle-import") (part "rcl_334_R-US_R0603"))
    )
    (comp (ref "U7")
      (value "TQP3M9035")
      (footprint "eagle-import:DFN-8")
      (fields (field (name "MFR") "Qorvo") (field (name "MPN") "TQP3M9035"))
      (libsource (lib "eagle-import") (part "TQP3M9035"))
    )
    (comp (ref "C9")
      (value "100p")
      (footprint "eagle-import:.0402-B-NOSILK")
      (fields (field (name "MPN") "GCM1555C1H101JA16D "))
      (libsource (lib "eagle-import") (part "C-EU0402-B-NOSILK"))
    )
    (comp (ref "C10")
      (value "100n")
      (footprint "eagle-import:.0402-B-NOSILK")
      (fields (field (name "MPN") "CGA2B1X7R1C104K050BC"))
      (libsource (lib "eagle-import") (part "C-EU0402-B-NOSILK"))
    )
    (comp (ref "C11")
      (value "DNP")
      (footprint "eagle-import:.0402-B-NOSILK")
      (fields (field (name "MPN") "GCM1555C1H101JA16D "))
      (libsource (lib "eagle-import") (part "C-EU0402-B-NOSILK"))
    )
    (comp (ref "C12")
      (value "100p")
      (footprint "eagle-import:.0402-B-NOSILK")
      (fields (field (name "MPN") "GCM1555C1H101JA16D "))
      (libsource (lib "eagle-import") (part "C-EU0402-B-NOSILK"))
    )
    (comp (ref "C13")
      (value "100p")
      (footprint "eagle-import:.0402-B-NOSILK")
      (fields (field (name "MPN") "GCM1555C1H101JA16D "))
      (libsource (lib "eagle-import") (part "C-EU0402-B-NOSILK"))
    )
    (comp (ref "C14")
      (value "100n")
      (footprint "eagle-import:.0402-B-NOSILK")
      (fields (field (name "MPN") "CGA2B1X7R1C104K050BC"))
      (libsource (lib "eagle-import") (part "C-EU0402-B-NOSILK"))
    )
    (comp (ref "R1")
      (value "147")
      (footprint "eagle-import:R0603")
      (fields (field (name "MPN") "ERJ-3EKF1470V"))
      (libsource (lib "eagle-import") (part "rcl_334_R-US_R0603"))
    )
    (comp (ref "R2")
      (value "147")
      (footprint "eagle-import:R0603")
      (fields (field (name "MPN") "ERJ-3EKF1470V"))
      (libsource (lib "eagle-import") (part "rcl_334_R-US_R0603"))
    )
    (comp (ref "R3")
      (value "17.8")
      (footprint "eagle-import:R0603")
      (fields (field (name "MPN") "ERJ-3EKF17R8V"))
      (libsource (lib "eagle-import") (part "rcl_334_R-US_R0603"))
    )
    (comp (ref "R4")
      (value "294")
      (footprint "eagle-import:R0603")
      (fields (field (name "MPN") "ERJ-3EKF2940V"))
      (libsource (lib "eagle-import") (part "rcl_334_R-US_R0603"))
    )
    (comp (ref "R13")
      (value "10k")
      (footprint "eagle-import:.0402-B-NOSILK")
      (fields (field (name "MPN") "ERJ-2RKF1002X"))
      (libsource (lib "eagle-import") (part "R-US_0402-B-NOSILK"))
    )
    (comp (ref "R14")
      (value "5.62k")
      (footprint "eagle-import:.0402-B-NOSILK")
      (fields (field (name "MPN") "ERJ-2RKF5621X"))
      (libsource (lib "eagle-import") (part "R-US_0402-B-NOSILK"))
    )
    (comp (ref "R15")
      (value "10k")
      (footprint "eagle-import:.0402-B-NOSILK")
      (fields (field (name "MPN") "ERJ-2RKF1002X"))
      (libsource (lib "eagle-import") (part "R-US_0402-B-NOSILK"))
    )
    (comp (ref "R16")
      (value "5.62k")
      (footprint "eagle-import:.0402-B-NOSILK")
      (fields (field (name "MPN") "ERJ-2RKF5621X"))
      (libsource (lib "eagle-import") (part "R-US_0402-B-NOSILK"))
    )
    (comp (ref "U4")
      (value "QPC1022")
      (footprint "eagle-import:QPC1022")
      (fields (field (name "MFR") "Qorvo") (field (name "MPN") "QPC1022SR"))
      (libsource (lib "eagle-import") (part "QPC1022"))
    )
    (comp (ref "U5")
      (value "NC7S04M5")
      (footprint "eagle-import:SOT95P280X140-5N")
      (fields
        (field (name "MFR") "Fairchild Semiconductor")
        (field (name "MPN") "NC7S04M5XX")
        (field (name "MFR_1") "ON Semiconductor")
      )
      (libsource (lib "eagle-import") (part "NC7S04M5XX"))
    )
    (comp (ref "C15")
      (value "100nF")
      (footprint "eagle-import:C0603")
      (fields (field (name "MPN") "C0603C104K5RACAUTO "))
      (libsource (lib "eagle-import") (part "rcl_334_C-EUC0603"))
    )
    (comp (ref "C16")
      (value "100nF")
      (footprint "eagle-import:C0603")
      (fields (field (name "MPN") "C0603C104K5RACAUTO "))
      (libsource (lib "eagle-import") (part "rcl_334_C-EUC0603"))
    )
    (comp (ref "C17")
      (value "100nF")
      (footprint "eagle-import:C0603")
      (fields (field (name "MPN") "C0603C104K5RACAUTO "))
      (libsource (lib "eagle-import") (part "rcl_334_C-EUC0603"))
    )
    (comp (ref "C18")
      (value "100pF")
      (footprint "eagle-import:C0603")
      (fields (field (name "MPN") "GCM1885C1H101JA16D "))
      (libsource (lib "eagle-import") (part "rcl_334_C-EUC0603"))
    )
    (comp (ref "C19")
      (value "1000pF")
      (footprint "eagle-import:C0603")
      (fields (field (name "MPN") "CGA3E2C0G1H102J080AA"))
      (libsource (lib "eagle-import") (part "rcl_334_C-EUC0603"))
    )
    (comp (ref "C20")
      (value "100pF")
      (footprint "eagle-import:C0603")
      (fields (field (name "MPN") "GCM1885C1H101JA16D "))
      (libsource (lib "eagle-import") (part "rcl_334_C-EUC0603"))
    )
    (comp (ref "C21")
      (value "3.0pF")
      (footprint "eagle-import:C0402")
      (fields (field (name "MPN") "UVK105CG030JW-F"))
      (libsource (lib "eagle-import") (part "rcl_334_C-EUC0402"))
    )
    (comp (ref "C22")
      (value "2.2pF")
      (footprint "eagle-import:C0402")
      (fields (field (name "MPN") "UVK105CG2R2JW-F"))
      (libsource (lib "eagle-import") (part "rcl_334_C-EUC0402"))
    )
    (comp (ref "C23")
      (value "1.6pF")
      (footprint "eagle-import:C0402")
      (fields (field (name "MPN") "GJM1555C1H1R6BB01D"))
      (libsource (lib "eagle-import") (part "rcl_334_C-EUC0402"))
    )
    (comp (ref "C24")
      (value "4.7pF")
      (footprint "eagle-import:C0603")
      (fields (field (name "MPN") "06032U4R7BAT2A "))
      (libsource (lib "eagle-import") (part "rcl_334_C-EUC0603"))
    )
    (comp (ref "L1")
      (value "10nH")
      (footprint "eagle-import:INDC2928X203N")
      (fields (field (name "MFR") "COILCRAFT") (field (name "MPN") "1008HQ-10NXJLB"))
      (libsource (lib "eagle-import") (part "1008HQ-10NXJLB"))
    )
    (comp (ref "L2")
      (value "6.8nH")
      (footprint "eagle-import:0805CS")
      (fields (field (name "MFR") "COILCRAFT") (field (name "MPN") "0805CS-060XJLC"))
      (libsource (lib "eagle-import") (part "0805CS-060XJLC"))
    )
    (comp (ref "L3")
      (value "1.2nH")
      (footprint "eagle-import:0402CS1N2XJLW")
      (fields (field (name "MFR") "COILCRAFT") (field (name "MPN") "0402CS-1N2XJLW"))
      (libsource (lib "eagle-import") (part "0402CS-1N2XJLW"))
    )
    (comp (ref "R17")
      (value "0")
      (footprint "eagle-import:R0805")
      (fields (field (name "MPN") "ERJ-6GEY0R00V"))
      (libsource (lib "eagle-import") (part "rcl_334_R-US_R0805"))
    )
    (comp (ref "R18")
      (value "1.2")
      (footprint "eagle-import:R0402")
      (fields (field (name "MPN") "ERJ-2GEJ1R2X"))
      (libsource (lib "eagle-import") (part "rcl_334_R-US_R0402"))
    )
    (comp (ref "R19")
      (value "110")
      (footprint "eagle-import:R0603")
      (fields (field (name "MPN") "ERJ-3EKF1100V"))
      (libsource (lib "eagle-import") (part "rcl_334_R-US_R0603"))
    )
    (comp (ref "R20")
      (value "220")
      (footprint "eagle-import:R0603")
      (fields (field (name "MPN") "ERJ-3EKF2200V"))
      (libsource (lib "eagle-import") (part "rcl_334_R-US_R0603"))
    )
    (comp (ref "U6")
      (value "TQP9111")
      (footprint "eagle-import:SAMACSYS_PARTS_QFN50P400X400X102-21N")
      (libsource (lib "eagle-import") (part "TQP9111"))
    )
    (comp (ref "C42")
      (value "15p")
      (footprint "eagle-import:.0402-B-NOSILK")
      (fields (field (name "MPN") "GJM1555C1H150JB01D "))
      (libsource (lib "eagle-import") (part "C-EU0402-B-NOSILK"))
    )
    (comp (ref "CF1")
      (value "CON-MMCX-F-MOLEX-0734151001")
      (footprint "eagle-import:CON-MMCX-F-MOLEX-0734151001")
      (fields (field (name "MPN") "0734151001"))
      (libsource (lib "eagle-import") (part "CON-MMCX-F-MOLEX-0734151001"))
    )
    (comp (ref "FL3")
      (value "885071-A")
      (footprint "eagle-import:FIL_B39162B9417K610")
      (fields (field (name "MFR") "Qorvo") (field (name "MPN") "885071-A"))
      (libsource (lib "eagle-import") (part "885071-A"))
    )
    (comp (ref "J4")
      (value "73415-2061")
      (footprint "eagle-import:73415-2063")
      (fields (field (name "MFR") "Molex") (field (name "MPN") "0734152061"))
      (libsource (lib "eagle-import") (part "73415-2061"))
    )
    (comp (ref "J5")
      (value "73415-2061")
      (footprint "eagle-import:73415-2063")
      (fields (field (name "MFR") "Molex") (field (name "MPN") "0734152061"))
      (libsource (lib "eagle-import") (part "73415-2061"))
    )
    (comp (ref "J6")
      (value "73415-2061")
      (footprint "eagle-import:73415-2063")
      (fields (field (name "MFR") "Molex") (field (name "MPN") "0734152061"))
      (libsource (lib "eagle-import") (part "73415-2061"))
    )
    (comp (ref "J7")
      (value "73415-2061")
      (footprint "eagle-import:73415-2063")
      (fields (field (name "MFR") "Molex") (field (name "MPN") "0734152061"))
      (libsource (lib "eagle-import") (part "73415-2061"))
    )
    (comp (ref "J8")
      (value "73415-2061")
      (footprint "eagle-import:73415-2063")
      (fields (field (name "MFR") "Molex") (field (name "MPN") "0734152061"))
      (libsource (lib "eagle-import") (part "73415-2061"))
    )
    (comp (ref "J10")
      (value "73415-2061")
      (footprint "eagle-import:73415-2063")
      (fields (field (name "MFR") "Molex") (field (name "MPN") "0734152061"))
      (libsource (lib "eagle-import") (part "73415-2061"))
    )
    (comp (ref "J11")
      (value "73415-2061")
      (footprint "eagle-import:73415-2063")
      (fields (field (name "MFR") "Molex") (field (name "MPN") "0734152061"))
      (libsource (lib "eagle-import") (part "73415-2061"))
    )
    (comp (ref "J12")
      (value "73415-2061")
      (footprint "eagle-import:73415-2063")
      (fields (field (name "MFR") "Molex") (field (name "MPN") "0734152061"))
      (libsource (lib "eagle-import") (part "73415-2061"))
    )
    (comp (ref "L11")
      (value "7.5nH")
      (footprint "eagle-import:0402CS1N2XJLW")
      (fields
        (field (name "MFR") "COILCRAFT")
        (field (name "MPN") "0402CS-1N2XJLW")
        (field (name "MPN_1") "0402CS-7N5XGLU")
      )
      (libsource (lib "eagle-import") (part "0402CS-1N2XJLW"))
    )
    (comp (ref "L12")
      (value "8.2nH")
      (footprint "eagle-import:0402CS1N2XJLW")
      (fields
        (field (name "MFR") "COILCRAFT")
        (field (name "MPN") "0402CS-1N2XJLW")
        (field (name "MPN_1") "0402CS-8N2XGLU")
      )
      (libsource (lib "eagle-import") (part "0402CS-1N2XJLW"))
    )
    (comp (ref "R33")
      (value "49.9")
      (footprint "eagle-import:R0603")
      (fields (field (name "MPN") "ERJ-3EKF49R9V"))
      (libsource (lib "eagle-import") (part "rcl_334_R-US_R0603"))
    )
    (comp (ref "R34")
      (value "49.9")
      (footprint "eagle-import:R0603")
      (fields (field (name "MPN") "ERJ-3EKF49R9V"))
      (libsource (lib "eagle-import") (part "rcl_334_R-US_R0603"))
    )
    (comp (ref "R35")
      (value "0")
      (footprint "eagle-import:.0402-B-NOSILK")
      (fields (field (name "MPN") "ERJ-2GE0R00X"))
      (libsource (lib "eagle-import") (part "R-US_0402-B-NOSILK"))
    )
    (comp (ref "R38")
      (value "49.9")
      (footprint "eagle-import:R0603")
      (fields (field (name "MPN") "MCT06030C4999FP500"))
      (libsource (lib "eagle-import") (part "rcl_334_R-US_R0603"))
    )
  )
  (nets
    (net (code "1") (name "+5V") (class "Default")
      (node (ref "C10") (pin "1") (pinfunction "1_1") (pintype "passive"))
      (node (ref "C13") (pin "1") (pinfunction "1_1") (pintype "passive"))
      (node (ref "C14") (pin "1") (pinfunction "1_1") (pintype "passive"))
      (node (ref "C3") (pin "1") (pinfunction "1_1") (pintype "passive"))
      (node (ref "C30") (pin "1") (pinfunction "1_1") (pintype "passive"))
      (node (ref "C31") (pin "1") (pinfunction "1_1") (pintype "passive"))
      (node (ref "C36") (pin "1") (pinfunction "1_1") (pintype "passive"))
      (node (ref "C39") (pin "1") (pinfunction "1_1") (pintype "passive"))
      (node (ref "C4") (pin "1") (pinfunction "1_1") (pintype "passive"))
      (node (ref "C40") (pin "1") (pinfunction "1_1") (pintype "passive"))
      (node (ref "C41") (pin "1") (pinfunction "1_1") (pintype "passive"))
      (node (ref "C5") (pin "1") (pinfunction "1_1") (pintype "passive"))
      (node (ref "C6") (pin "1") (pinfunction "1_1") (pintype "passive"))
      (node (ref "C7") (pin "1") (pinfunction "1_1") (pintype "passive"))
      (node (ref "C8") (pin "1") (pinfunction "1_1") (pintype "passive"))
      (node (ref "C9") (pin "1") (pinfunction "1_1") (pintype "passive"))
      (node (ref "J3") (pin "4") (pinfunction "4_4") (pintype "passive"))
      (node (ref "LED2") (pin "2") (pinfunction "A_2") (pintype "bidirectional"))
      (node (ref "R13") (pin "1") (pinfunction "1_1") (pintype "passive"))
      (node (ref "R17") (pin "2") (pinfunction "2_2") (pintype "passive"))
      (node (ref "R23") (pin "2") (pinfunction "2_2") (pintype "passive"))
      (node (ref "R24") (pin "1") (pinfunction "1_1") (pintype "passive"))
      (node (ref "R9") (pin "2") (pinfunction "2_2") (pintype "passive"))
      (node (ref "S1") (pin "1") (pinfunction "1_1") (pintype "bidirectional"))
      (node (ref "U1") (pin "6") (pinfunction "VCC_6") (pintype "power_in"))
      (node (ref "U10") (pin "5") (pinfunction "VCC_5") (pintype "bidirectional"))
      (node (ref "U11") (pin "5") (pinfunction "VCC_5") (pintype "bidirectional"))
      (node (ref "U2") (pin "5") (pinfunction "V+_5") (pintype "power_in"))
      (node (ref "U3") (pin "4") (pinfunction "DIV_4") (pintype "input"))
      (node (ref "U3") (pin "5") (pinfunction "V+_5") (pintype "power_in"))
      (node (ref "U4") (pin "7") (pinfunction "VDD_7") (pintype "power_in"))
      (node (ref "U5") (pin "5") (pinfunction "VCC_5") (pintype "power_in"))
      (node (ref "U8") (pin "7") (pinfunction "VDD_7") (pintype "power_in"))
    )
    (net (code "2") (name "FORCE_BRDCST_+3.3V") (class "Default")
      (node (ref "J9") (pin "1") (pinfunction "1_1") (pintype "passive"))
      (node (ref "J9") (pin "3") (pinfunction "3_3") (pintype "passive"))
      (node (ref "R37") (pin "2") (pinfunction "2_2") (pintype "passive"))
      (node (ref "U11") (pin "2") (pinfunction "A_2") (pintype "bidirectional"))
    )
    (net (code "3") (name "FORCE_BRDCST_+5V") (class "Default")
      (node (ref "U10") (pin "2") (pinfunction "B_2") (pintype "bidirectional"))
      (node (ref "U11") (pin "4") (pinfunction "Y_4") (pintype "bidirectional"))
    )
    (net (code "4") (name "GND") (class "Default")
      (node (ref "C10") (pin "2") (pinfunction "2_2") (pintype "passive"))
      (node (ref "C11") (pin "2") (pinfunction "2_2") (pintype "passive"))
      (node (ref "C12") (pin "2") (pinfunction "2_2") (pintype "passive"))
      (node (ref "C13") (pin "2") (pinfunction "2_2") (pintype "passive"))
      (node (ref "C14") (pin "2") (pinfunction "2_2") (pintype "passive"))
      (node (ref "C15") (pin "2") (pinfunction "2_2") (pintype "passive"))
      (node (ref "C16") (pin "2") (pinfunction "2_2") (pintype "passive"))
      (node (ref "C17") (pin "2") (pinfunction "2_2") (pintype "passive"))
      (node (ref "C18") (pin "2") (pinfunction "2_2") (pintype "passive"))
      (node (ref "C19") (pin "2") (pinfunction "2_2") (pintype "passive"))
      (node (ref "C2") (pin "2") (pinfunction "2_2") (pintype "passive"))
      (node (ref "C21") (pin "2") (pinfunction "2_2") (pintype "passive"))
      (node (ref "C22") (pin "2") (pinfunction "2_2") (pintype "passive"))
      (node (ref "C23") (pin "2") (pinfunction "2_2") (pintype "passive"))
      (node (ref "C25") (pin "2") (pinfunction "2_2") (pintype "passive"))
      (node (ref "C27") (pin "1") (pinfunction "1_1") (pintype "passive"))
      (node (ref "C29") (pin "2") (pinfunction "2_2") (pintype "passive"))
      (node (ref "C3") (pin "2") (pinfunction "2_2") (pintype "passive"))
      (node (ref "C30") (pin "2") (pinfunction "2_2") (pintype "passive"))
      (node (ref "C31") (pin "2") (pinfunction "2_2") (pintype "passive"))
      (node (ref "C32") (pin "2") (pinfunction "2_2") (pintype "passive"))
      (node (ref "C33") (pin "2") (pinfunction "2_2") (pintype "passive"))
      (node (ref "C34") (pin "2") (pinfunction "2_2") (pintype "passive"))
      (node (ref "C35") (pin "2") (pinfunction "2_2") (pintype "passive"))
      (node (ref "C36") (pin "2") (pinfunction "2_2") (pintype "passive"))
      (node (ref "C37") (pin "2") (pinfunction "2_2") (pintype "passive"))
      (node (ref "C38") (pin "2") (pinfunction "2_2") (pintype "passive"))
      (node (ref "C39") (pin "2") (pinfunction "2_2") (pintype "passive"))
      (node (ref "C4") (pin "2") (pinfunction "2_2") (pintype "passive"))
      (node (ref "C40") (pin "2") (pinfunction "2_2") (pintype "passive"))
      (node (ref "C41") (pin "2") (pinfunction "2_2") (pintype "passive"))
      (node (ref "C5") (pin "2") (pinfunction "2_2") (pintype "passive"))
      (node (ref "C6") (pin "2") (pinfunction "2_2") (pintype "passive"))
      (node (ref "C7") (pin "2") (pinfunction "2_2") (pintype "passive"))
      (node (ref "C8") (pin "2") (pinfunction "2_2") (pintype "passive"))
      (node (ref "C9") (pin "2") (pinfunction "2_2") (pintype "passive"))
      (node (ref "CF1") (pin "G1") (pinfunction "SHIELD_G1") (pintype "passive"))
      (node (ref "CF1") (pin "G2") (pinfunction "SHIELD_G2") (pintype "passive"))
      (node (ref "CF1") (pin "G3") (pinfunction "SHIELD_G3") (pintype "passive"))
      (node (ref "CF1") (pin "G4") (pinfunction "SHIELD_G4") (pintype "passive"))
      (node (ref "FL1") (pin "2") (pinfunction "GND_2") (pintype "power_in"))
      (node (ref "FL1") (pin "3") (pinfunction "GND_3") (pintype "power_in"))
      (node (ref "FL1") (pin "5") (pinfunction "GND_5") (pintype "power_in"))
      (node (ref "FL2") (pin "2") (pinfunction "GND_2") (pintype "power_in"))
      (node (ref "FL2") (pin "3") (pinfunction "GND_3") (pintype "power_in"))
      (node (ref "FL2") (pin "5") (pinfunction "GND_5") (pintype "power_in"))
      (node (ref "FL3") (pin "2") (pinfunction "GND_2") (pintype "power_in"))
      (node (ref "FL3") (pin "3") (pinfunction "GND_3") (pintype "power_in"))
      (node (ref "FL3") (pin "5") (pinfunction "GND_5") (pintype "power_in"))
      (node (ref "J1") (pin "2") (pinfunction "GND_2") (pintype "passive"))
      (node (ref "J1") (pin "3") (pinfunction "GND_3") (pintype "passive"))
      (node (ref "J1") (pin "4") (pinfunction "GND_4") (pintype "passive"))
      (node (ref "J1") (pin "5") (pinfunction "GND_5") (pintype "passive"))
      (node (ref "J10") (pin "2") (pinfunction "GND_2") (pintype "passive"))
      (node (ref "J10") (pin "3") (pinfunction "GND_3") (pintype "passive"))
      (node (ref "J10") (pin "4") (pinfunction "GND_4") (pintype "passive"))
      (node (ref "J10") (pin "5") (pinfunction "GND_5") (pintype "passive"))
      (node (ref "J11") (pin "2") (pinfunction "GND_2") (pintype "passive"))
      (node (ref "J11") (pin "3") (pinfunction "GND_3") (pintype "passive"))
      (node (ref "J11") (pin "4") (pinfunction "GND_4") (pintype "passive"))
      (node (ref "J11") (pin "5") (pinfunction "GND_5") (pintype "passive"))
      (node (ref "J12") (pin "2") (pinfunction "GND_2") (pintype "passive"))
      (node (ref "J12") (pin "3") (pinfunction "GND_3") (pintype "passive"))
      (node (ref "J12") (pin "4") (pinfunction "GND_4") (pintype "passive"))
      (node (ref "J12") (pin "5") (pinfunction "GND_5") (pintype "passive"))
      (node (ref "J2") (pin "2") (pinfunction "GND_2") (pintype "passive"))
      (node (ref "J2") (pin "3") (pinfunction "GND_3") (pintype "passive"))
      (node (ref "J2") (pin "4") (pinfunction "GND_4") (pintype "passive"))
      (node (ref "J2") (pin "5") (pinfunction "GND_5") (pintype "passive"))
      (node (ref "J3") (pin "7") (pinfunction "7_7") (pintype "passive"))
      (node (ref "J3") (pin "8") (pinfunction "8_8") (pintype "passive"))
      (node (ref "J4") (pin "2") (pinfunction "GND_2") (pintype "passive"))
      (node (ref "J4") (pin "3") (pinfunction "GND_3") (pintype "passive"))
      (node (ref "J4") (pin "4") (pinfunction "GND_4") (pintype "passive"))
      (node (ref "J4") (pin "5") (pinfunction "GND_5") (pintype "passive"))
      (node (ref "J5") (pin "2") (pinfunction "GND_2") (pintype "passive"))
      (node (ref "J5") (pin "3") (pinfunction "GND_3") (pintype "passive"))
      (node (ref "J5") (pin "4") (pinfunction "GND_4") (pintype "passive"))
      (node (ref "J5") (pin "5") (pinfunction "GND_5") (pintype "passive"))
      (node (ref "J6") (pin "2") (pinfunction "GND_2") (pintype "passive"))
      (node (ref "J6") (pin "3") (pinfunction "GND_3") (pintype "passive"))
      (node (ref "J6") (pin "4") (pinfunction "GND_4") (pintype "passive"))
      (node (ref "J6") (pin "5") (pinfunction "GND_5") (pintype "passive"))
      (node (ref "J7") (pin "2") (pinfunction "GND_2") (pintype "passive"))
      (node (ref "J7") (pin "3") (pinfunction "GND_3") (pintype "passive"))
      (node (ref "J7") (pin "4") (pinfunction "GND_4") (pintype "passive"))
      (node (ref "J7") (pin "5") (pinfunction "GND_5") (pintype "passive"))
      (node (ref "J8") (pin "2") (pinfunction "GND_2") (pintype "passive"))
      (node (ref "J8") (pin "3") (pinfunction "GND_3") (pintype "passive"))
      (node (ref "J8") (pin "4") (pinfunction "GND_4") (pintype "passive"))
      (node (ref "J8") (pin "5") (pinfunction "GND_5") (pintype "passive"))
      (node (ref "J9") (pin "2") (pinfunction "2_2") (pintype "passive"))
      (node (ref "L11") (pin "1") (pinfunction "1_1") (pintype "bidirectional"))
      (node (ref "L12") (pin "1") (pinfunction "1_1") (pintype "bidirectional"))
      (node (ref "L5") (pin "1") (pinfunction "1_1") (pintype "bidirectional"))
      (node (ref "L6") (pin "1") (pinfunction "1_1") (pintype "bidirectional"))
      (node (ref "L7") (pin "1") (pinfunction "1_1") (pintype "bidirectional"))
      (node (ref "L8") (pin "1") (pinfunction "1_1") (pintype "bidirectional"))
      (node (ref "PD1") (pin "1") (pinfunction "GND_1") (pintype "power_in"))
      (node (ref "PD1") (pin "3") (pinfunction "GND_3") (pintype "power_in"))
      (node (ref "PD1") (pin "5") (pinfunction "GND_5") (pintype "power_in"))
      (node (ref "R10") (pin "1") (pinfunction "1_1") (pintype "passive"))
      (node (ref "R11") (pin "1") (pinfunction "1_1") (pintype "passive"))
      (node (ref "R12") (pin "1") (pinfunction "1_1") (pintype "passive"))
      (node (ref "R14") (pin "2") (pinfunction "2_2") (pintype "passive"))
      (node (ref "R16") (pin "2") (pinfunction "2_2") (pintype "passive"))
      (node (ref "R2") (pin "1") (pinfunction "1_1") (pintype "passive"))
      (node (ref "R22") (pin "1") (pinfunction "1_1") (pintype "passive"))
      (node (ref "R25") (pin "2") (pinfunction "2_2") (pintype "passive"))
      (node (ref "R27") (pin "2") (pinfunction "2_2") (pintype "passive"))
      (node (ref "R29") (pin "1") (pinfunction "1_1") (pintype "passive"))
      (node (ref "R32") (pin "1") (pinfunction "1_1") (pintype "passive"))
      (node (ref "R33") (pin "1") (pinfunction "1_1") (pintype "passive"))
      (node (ref "R34") (pin "1") (pinfunction "1_1") (pintype "passive"))
      (node (ref "R36") (pin "1") (pinfunction "1_1") (pintype "passive"))
      (node (ref "R37") (pin "1") (pinfunction "1_1") (pintype "passive"))
      (node (ref "R38") (pin "1") (pinfunction "1_1") (pintype "passive"))
      (node (ref "R4") (pin "2") (pinfunction "2_2") (pintype "passive"))
      (node (ref "R6") (pin "1") (pinfunction "1_1") (pintype "passive"))
      (node (ref "R8") (pin "2") (pinfunction "2_2") (pintype "passive"))
      (node (ref "S1") (pin "6") (pinfunction "6_6") (pintype "bidirectional"))
      (node (ref "U1") (pin "2") (pinfunction "GND_2") (pintype "power_in"))
      (node (ref "U1") (pin "4") (pinfunction "LEN_4") (pintype "input"))
      (node (ref "U10") (pin "3") (pinfunction "GND_3") (pintype "bidirectional"))
      (node (ref "U11") (pin "3") (pinfunction "GND_3") (pintype "bidirectional"))
      (node (ref "U2") (pin "2") (pinfunction "GND_2") (pintype "power_in"))
      (node (ref "U2") (pin "4") (pinfunction "DIV_4") (pintype "input"))
      (node (ref "U3") (pin "2") (pinfunction "GND_2") (pintype "power_in"))
      (node (ref "U4") (pin "1") (pinfunction "GND_1") (pintype "power_in"))
      (node (ref "U4") (pin "3") (pinfunction "GND_3") (pintype "power_in"))
      (node (ref "U4") (pin "9") (pinfunction "GND_9") (pintype "power_in"))
      (node (ref "U5") (pin "3") (pinfunction "GND_3") (pintype "power_in"))
      (node (ref "U6") (pin "1") (pinfunction "GND_1") (pintype "bidirectional"))
      (node (ref "U6") (pin "10") (pinfunction "GND_10") (pintype "bidirectional"))
      (node (ref "U6") (pin "11") (pinfunction "GND_11") (pintype "bidirectional"))
      (node (ref "U6") (pin "15") (pinfunction "GND_15") (pintype "bidirectional"))
      (node (ref "U6") (pin "17") (pinfunction "GND_17") (pintype "bidirectional"))
      (node (ref "U6") (pin "19") (pinfunction "GND_19") (pintype "bidirectional"))
      (node (ref "U6") (pin "21") (pinfunction "GND_21") (pintype "bidirectional"))
      (node (ref "U6") (pin "5") (pinfunction "GND_5") (pintype "bidirectional"))
      (node (ref "U6") (pin "7") (pinfunction "GND_7") (pintype "bidirectional"))
      (node (ref "U6") (pin "9") (pinfunction "GND_9") (pintype "bidirectional"))
      (node (ref "U7") (pin "9") (pinfunction "GND_9") (pintype "power_in"))
      (node (ref "U8") (pin "1") (pinfunction "GND_1") (pintype "power_in"))
      (node (ref "U8") (pin "3") (pinfunction "GND_3") (pintype "power_in"))
      (node (ref "U8") (pin "9") (pinfunction "GND_9") (pintype "power_in"))
      (node (ref "U9") (pin "1") (pinfunction "GND_1") (pintype "power_in"))
      (node (ref "U9") (pin "10") (pinfunction "GND_10") (pintype "power_in"))
      (node (ref "U9") (pin "11") (pinfunction "GND_11") (pintype "passive"))
      (node (ref "U9") (pin "7") (pinfunction "GND_7") (pintype "power_in"))
    )
    (net (code "5") (name "Net-(C1-Pad1)") (class "Default")
      (node (ref "C1") (pin "1") (pinfunction "1_1") (pintype "passive"))
      (node (ref "R7") (pin "2") (pinfunction "2_2") (pintype "passive"))
      (node (ref "R8") (pin "1") (pinfunction "1_1") (pintype "passive"))
    )
    (net (code "6") (name "Net-(C15-Pad1)") (class "Default")
      (node (ref "C15") (pin "1") (pinfunction "1_1") (pintype "passive"))
      (node (ref "C16") (pin "1") (pinfunction "1_1") (pintype "passive"))
      (node (ref "C17") (pin "1") (pinfunction "1_1") (pintype "passive"))
      (node (ref "C19") (pin "1") (pinfunction "1_1") (pintype "passive"))
      (node (ref "L1") (pin "2") (pinfunction "2_2") (pintype "bidirectional"))
      (node (ref "L2") (pin "2") (pinfunction "2_2") (pintype "bidirectional"))
      (node (ref "R17") (pin "1") (pinfunction "1_1") (pintype "passive"))
      (node (ref "R20") (pin "2") (pinfunction "2_2") (pintype "passive"))
    )
    (net (code "7") (name "Net-(C20-Pad1)") (class "Default")
      (node (ref "C20") (pin "1") (pinfunction "1_1") (pintype "passive"))
      (node (ref "C23") (pin "1") (pinfunction "1_1") (pintype "passive"))
      (node (ref "L3") (pin "2") (pinfunction "2_2") (pintype "bidirectional"))
    )
    (net (code "8") (name "Net-(C22-Pad1)") (class "Default")
      (node (ref "C22") (pin "1") (pinfunction "1_1") (pintype "passive"))
      (node (ref "C24") (pin "2") (pinfunction "2_2") (pintype "passive"))
      (node (ref "R18") (pin "1") (pinfunction "1_1") (pintype "passive"))
    )
    (net (code "9") (name "Net-(C27-Pad2)") (class "Default")
      (node (ref "C27") (pin "2") (pinfunction "2_2") (pintype "passive"))
      (node (ref "C29") (pin "1") (pinfunction "1_1") (pintype "passive"))
      (node (ref "L4") (pin "2") (pinfunction "2_2") (pintype "bidirectional"))
      (node (ref "R23") (pin "1") (pinfunction "1_1") (pintype "passive"))
    )
    (net (code "10") (name "Net-(C35-Pad1)") (class "Default")
      (node (ref "C35") (pin "1") (pinfunction "1_1") (pintype "passive"))
      (node (ref "J3") (pin "5") (pinfunction "5_5") (pintype "passive"))
      (node (ref "J3") (pin "6") (pinfunction "6_6") (pintype "passive"))
    )
    (net (code "11") (name "Net-(C37-Pad1)") (class "Default")
      (node (ref "C37") (pin "1") (pinfunction "1_1") (pintype "passive"))
      (node (ref "R30") (pin "1") (pinfunction "1_1") (pintype "passive"))
    )
    (net (code "12") (name "Net-(CF1-PadCENTER)") (class "Default")
      (node (ref "CF1") (pin "CENTER") (pinfunction "CENTER_CENTER") (pintype "passive"))
      (node (ref "R34") (pin "2") (pinfunction "2_2") (pintype "passive"))
    )
    (net (code "13") (name "Net-(FL1-OUT)") (class "Default")
      (node (ref "C26") (pin "1") (pinfunction "1_1") (pintype "passive"))
      (node (ref "FL1") (pin "4") (pinfunction "OUT_4") (pintype "passive"))
      (node (ref "L6") (pin "2") (pinfunction "2_2") (pintype "bidirectional"))
    )
    (net (code "14") (name "Net-(FL2-IN)") (class "Default")
      (node (ref "C28") (pin "2") (pinfunction "2_2") (pintype "passive"))
      (node (ref "FL2") (pin "1") (pinfunction "IN_1") (pintype "passive"))
      (node (ref "L7") (pin "2") (pinfunction "2_2") (pintype "bidirectional"))
    )
    (net (code "15") (name "Net-(FL3-IN)") (class "Default")
      (node (ref "FL3") (pin "1") (pinfunction "IN_1") (pintype "passive"))
      (node (ref "J4") (pin "1") (pinfunction "CTR_1") (pintype "passive"))
      (node (ref "L11") (pin "2") (pinfunction "2_2") (pintype "bidirectional"))
    )
    (net (code "16") (name "Net-(FL3-OUT)") (class "Default")
      (node (ref "FL3") (pin "4") (pinfunction "OUT_4") (pintype "passive"))
      (node (ref "L12") (pin "2") (pinfunction "2_2") (pintype "bidirectional"))
      (node (ref "R35") (pin "1") (pinfunction "1_1") (pintype "passive"))
    )
    (net (code "17") (name "Net-(J1-CTR)") (class "Default")
      (node (ref "J1") (pin "1") (pinfunction "CTR_1") (pintype "passive"))
      (node (ref "PD1") (pin "2") (pinfunction "IN_2") (pintype "input"))
    )
    (net (code "18") (name "Net-(J2-CTR)") (class "Default")
      (node (ref "J2") (pin "1") (pinfunction "CTR_1") (pintype "passive"))
      (node (ref "U8") (pin "2") (pinfunction "RF_COM_2") (pintype "bidirectional"))
    )
    (net (code "19") (name "Net-(J5-CTR)") (class "Default")
      (node (ref "J5") (pin "1") (pinfunction "CTR_1") (pintype "passive"))
      (node (ref "R35") (pin "2") (pinfunction "2_2") (pintype "passive"))
    )
    (net (code "20") (name "Net-(J6-CTR)") (class "Default")
      (node (ref "J6") (pin "1") (pinfunction "CTR_1") (pintype "passive"))
      (node (ref "J7") (pin "1") (pinfunction "CTR_1") (pintype "passive"))
    )
    (net (code "21") (name "Net-(J8-CTR)") (class "Default")
      (node (ref "J8") (pin "1") (pinfunction "CTR_1") (pintype "passive"))
      (node (ref "R33") (pin "2") (pinfunction "2_2") (pintype "passive"))
    )
    (net (code "22") (name "Net-(J10-CTR)") (class "Default")
      (node (ref "C42") (pin "1") (pinfunction "1_1") (pintype "passive"))
      (node (ref "J10") (pin "1") (pinfunction "CTR_1") (pintype "passive"))
    )
    (net (code "23") (name "Net-(J11-CTR)") (class "Default")
      (node (ref "C42") (pin "2") (pinfunction "2_2") (pintype "passive"))
      (node (ref "J11") (pin "1") (pinfunction "CTR_1") (pintype "passive"))
    )
    (net (code "24") (name "Net-(J12-CTR)") (class "Default")
      (node (ref "J12") (pin "1") (pinfunction "CTR_1") (pintype "passive"))
      (node (ref "R38") (pin "2") (pinfunction "2_2") (pintype "passive"))
    )
    (net (code "25") (name "Net-(LED1-A)") (class "Default")
      (node (ref "LED1") (pin "2") (pinfunction "A_2") (pintype "bidirectional"))
      (node (ref "S1") (pin "2") (pinfunction "2_2") (pintype "bidirectional"))
      (node (ref "U2") (pin "1") (pinfunction "IN_1") (pintype "input"))
      (node (ref "U3") (pin "1") (pinfunction "IN_1") (pintype "input"))
    )
    (net (code "26") (name "Net-(LED1-K)") (class "Default")
      (node (ref "LED1") (pin "1") (pinfunction "K_1") (pintype "bidirectional"))
      (node (ref "R32") (pin "2") (pinfunction "2_2") (pintype "passive"))
    )
    (net (code "27") (name "Net-(LED2-K)") (class "Default")
      (node (ref "LED2") (pin "1") (pinfunction "K_1") (pintype "bidirectional"))
      (node (ref "R36") (pin "2") (pinfunction "2_2") (pintype "passive"))
    )
    (net (code "28") (name "Net-(PD1-OUT1)") (class "Default")
      (node (ref "PD1") (pin "4") (pinfunction "OUT1_4") (pintype "output"))
      (node (ref "R39") (pin "1") (pinfunction "1_1") (pintype "passive"))
      (node (ref "R5") (pin "2") (pinfunction "2_2") (pintype "passive"))
      (node (ref "R7") (pin "1") (pinfunction "1_1") (pintype "passive"))
    )
    (net (code "29") (name "Net-(R1-Pad1)") (class "Default")
      (node (ref "R1") (pin "1") (pinfunction "1_1") (pintype "passive"))
      (node (ref "R2") (pin "2") (pinfunction "2_2") (pintype "passive"))
    )
    (net (code "30") (name "Net-(R5-Pad1)") (class "Default")
      (node (ref "R5") (pin "1") (pinfunction "1_1") (pintype "passive"))
      (node (ref "R6") (pin "2") (pinfunction "2_2") (pintype "passive"))
    )
    (net (code "31") (name "Net-(S1-Pad3)") (class "Default")
      (node (ref "S1") (pin "3") (pinfunction "3_3") (pintype "bidirectional"))
      (node (ref "S1") (pin "5") (pinfunction "5_5") (pintype "bidirectional"))
    )
    (net (code "32") (name "Net-(U1-RFIN)") (class "Default")
      (node (ref "C1") (pin "2") (pinfunction "2_2") (pintype "passive"))
      (node (ref "U1") (pin "1") (pinfunction "RFIN_1") (pintype "input"))
    )
    (net (code "33") (name "Net-(U1-VM)") (class "Default")
      (node (ref "C2") (pin "1") (pinfunction "1_1") (pintype "passive"))
      (node (ref "R10") (pin "2") (pinfunction "2_2") (pintype "passive"))
      (node (ref "R9") (pin "1") (pinfunction "1_1") (pintype "passive"))
      (node (ref "U1") (pin "3") (pinfunction "VM_3") (pintype "input"))
    )
    (net (code "34") (name "Net-(U1-VOUT)") (class "Default")
      (node (ref "U1") (pin "5") (pinfunction "VOUT_5") (pintype "output"))
      (node (ref "U10") (pin "1") (pinfunction "A_1") (pintype "bidirectional"))
    )
    (net (code "35") (name "Net-(U2-SET)") (class "Default")
      (node (ref "R11") (pin "2") (pinfunction "2_2") (pintype "passive"))
      (node (ref "U2") (pin "3") (pinfunction "SET_3") (pintype "input"))
    )
    (net (code "36") (name "Net-(U3-SET)") (class "Default")
      (node (ref "R12") (pin "2") (pinfunction "2_2") (pintype "passive"))
      (node (ref "U3") (pin "3") (pinfunction "SET_3") (pintype "input"))
    )
    (net (code "37") (name "Net-(U4-CTRL)") (class "Default")
      (node (ref "C11") (pin "1") (pinfunction "1_1") (pintype "passive"))
      (node (ref "R15") (pin "2") (pinfunction "2_2") (pintype "passive"))
      (node (ref "R16") (pin "1") (pinfunction "1_1") (pintype "passive"))
      (node (ref "U4") (pin "5") (pinfunction "CTRL_5") (pintype "bidirectional"))
    )
    (net (code "38") (name "Net-(U4-EN)") (class "Default")
      (node (ref "C12") (pin "1") (pinfunction "1_1") (pintype "passive"))
      (node (ref "R13") (pin "2") (pinfunction "2_2") (pintype "passive"))
      (node (ref "R14") (pin "1") (pinfunction "1_1") (pintype "passive"))
      (node (ref "U4") (pin "6") (pinfunction "EN_6") (pintype "bidirectional"))
    )
    (net (code "39") (name "Net-(U4-RF2)") (class "Default")
      (node (ref "R1") (pin "2") (pinfunction "2_2") (pintype "passive"))
      (node (ref "R3") (pin "1") (pinfunction "1_1") (pintype "passive"))
      (node (ref "U4") (pin "8") (pinfunction "RF2_8") (pintype "bidirectional"))
    )
    (net (code "40") (name "Net-(U5-Y)") (class "Default")
      (node (ref "R15") (pin "1") (pinfunction "1_1") (pintype "passive"))
      (node (ref "U5") (pin "4") (pinfunction "Y_4") (pintype "output"))
    )
    (net (code "41") (name "Net-(U6-IREF2)") (class "Default")
      (node (ref "C18") (pin "1") (pinfunction "1_1") (pintype "passive"))
      (node (ref "R19") (pin "2") (pinfunction "2_2") (pintype "passive"))
      (node (ref "U6") (pin "8") (pinfunction "IREF2_8") (pintype "bidirectional"))
    )
    (net (code "42") (name "Net-(U6-RFIN)") (class "Default")
      (node (ref "R18") (pin "2") (pinfunction "2_2") (pintype "passive"))
      (node (ref "U6") (pin "1_2_3") (pinfunction "RFIN_1_2_3") (pintype "bidirectional"))
    )
    (net (code "43") (name "Net-(U6-RFOUT)") (class "Default")
      (node (ref "C21") (pin "1") (pinfunction "1_1") (pintype "passive"))
      (node (ref "L3") (pin "1") (pinfunction "1_1") (pintype "bidirectional"))
      (node (ref "U6") (pin "13_14_15") (pinfunction "RFOUT_13_14_15") (pintype "bidirectional"))
    )
    (net (code "44") (name "Net-(U6-VBIAS)") (class "Default")
      (node (ref "R20") (pin "1") (pinfunction "1_1") (pintype "passive"))
      (node (ref "U6") (pin "16") (pinfunction "VBIAS_16") (pintype "bidirectional"))
    )
    (net (code "45") (name "Net-(U6-VCC1)") (class "Default")
      (node (ref "L2") (pin "1") (pinfunction "1_1") (pintype "bidirectional"))
      (node (ref "U6") (pin "20") (pinfunction "VCC1_20") (pintype "bidirectional"))
    )
    (net (code "46") (name "Net-(U6-VCC2)") (class "Default")
      (node (ref "L1") (pin "1") (pinfunction "1_1") (pintype "bidirectional"))
      (node (ref "U6") (pin "18") (pinfunction "VCC2_18") (pintype "bidirectional"))
    )
    (net (code "47") (name "Net-(U7-RFIN)") (class "Default")
      (node (ref "C26") (pin "2") (pinfunction "2_2") (pintype "passive"))
      (node (ref "U7") (pin "2") (pinfunction "RFIN_2") (pintype "bidirectional"))
    )
    (net (code "48") (name "Net-(U7-RFOUT)") (class "Default")
      (node (ref "C28") (pin "1") (pinfunction "1_1") (pintype "passive"))
      (node (ref "L4") (pin "1") (pinfunction "1_1") (pintype "bidirectional"))
      (node (ref "U7") (pin "7") (pinfunction "RFOUT_7") (pintype "bidirectional"))
    )
    (net (code "49") (name "Net-(U7-SHUTDN)") (class "Default")
      (node (ref "R21") (pin "1") (pinfunction "1_1") (pintype "passive"))
      (node (ref "R22") (pin "2") (pinfunction "2_2") (pintype "passive"))
      (node (ref "U7") (pin "6") (pinfunction "SHUTDN_6") (pintype "bidirectional"))
    )
    (net (code "50") (name "Net-(U8-CTRL)") (class "Default")
      (node (ref "C32") (pin "1") (pinfunction "1_1") (pintype "passive"))
      (node (ref "R26") (pin "2") (pinfunction "2_2") (pintype "passive"))
      (node (ref "R27") (pin "1") (pinfunction "1_1") (pintype "passive"))
      (node (ref "U8") (pin "5") (pinfunction "CTRL_5") (pintype "bidirectional"))
    )
    (net (code "51") (name "Net-(U8-EN)") (class "Default")
      (node (ref "C33") (pin "1") (pinfunction "1_1") (pintype "passive"))
      (node (ref "R24") (pin "2") (pinfunction "2_2") (pintype "passive"))
      (node (ref "R25") (pin "1") (pinfunction "1_1") (pintype "passive"))
      (node (ref "U8") (pin "6") (pinfunction "EN_6") (pintype "bidirectional"))
    )
    (net (code "52") (name "Net-(U9-FB)") (class "Default")
      (node (ref "R28") (pin "1") (pinfunction "1_1") (pintype "passive"))
      (node (ref "R29") (pin "2") (pinfunction "2_2") (pintype "passive"))
      (node (ref "U9") (pin "6") (pinfunction "FB_6") (pintype "passive"))
    )
    (net (code "53") (name "Net-(U9-SWA)") (class "Default")
      (node (ref "D1") (pin "A") (pinfunction "A_A") (pintype "passive"))
      (node (ref "L9") (pin "1") (pinfunction "1_1") (pintype "bidirectional"))
      (node (ref "U9") (pin "2") (pinfunction "SWA_2") (pintype "passive"))
    )
    (net (code "54") (name "Net-(U9-SWB)") (class "Default")
      (node (ref "D2") (pin "A") (pinfunction "A_A") (pintype "passive"))
      (node (ref "L10") (pin "1") (pinfunction "1_1") (pintype "bidirectional"))
      (node (ref "U9") (pin "9") (pinfunction "SWB_9") (pintype "passive"))
    )
    (net (code "55") (name "Net-(U9-VC)") (class "Default")
      (node (ref "C38") (pin "1") (pinfunction "1_1") (pintype "passive"))
      (node (ref "R30") (pin "2") (pinfunction "2_2") (pintype "passive"))
      (node (ref "U9") (pin "5") (pinfunction "VC_5") (pintype "output"))
    )
    (net (code "56") (name "Net-(U9-VIN)") (class "Default")
      (node (ref "C34") (pin "1") (pinfunction "1_1") (pintype "passive"))
      (node (ref "J3") (pin "2") (pinfunction "2_2") (pintype "passive"))
      (node (ref "L10") (pin "2") (pinfunction "2_2") (pintype "bidirectional"))
      (node (ref "L9") (pin "2") (pinfunction "2_2") (pintype "bidirectional"))
      (node (ref "R31") (pin "2") (pinfunction "2_2") (pintype "passive"))
      (node (ref "U9") (pin "8") (pinfunction "VIN_8") (pintype "input"))
    )
    (net (code "57") (name "Net-(U9-VOUT)") (class "Default")
      (node (ref "C25") (pin "1") (pinfunction "1_1") (pintype "passive"))
      (node (ref "D1") (pin "C") (pinfunction "C_C") (pintype "passive"))
      (node (ref "D2") (pin "C") (pinfunction "C_C") (pintype "passive"))
      (node (ref "J3") (pin "3") (pinfunction "3_3") (pintype "passive"))
      (node (ref "R28") (pin "2") (pinfunction "2_2") (pintype "passive"))
      (node (ref "U9") (pin "3") (pinfunction "VOUT_3") (pintype "output"))
    )
    (net (code "58") (name "Net-(U9-~{SHDN})") (class "Default")
      (node (ref "J3") (pin "1") (pinfunction "1_1") (pintype "passive"))
      (node (ref "R31") (pin "1") (pinfunction "1_1") (pintype "passive"))
      (node (ref "U9") (pin "4") (pinfunction "~{SHDN}_4") (pintype "passive"))
    )
    (net (code "59") (name "Net-(U10-Y)") (class "Default")
      (node (ref "S1") (pin "4") (pinfunction "4_4") (pintype "bidirectional"))
      (node (ref "U10") (pin "4") (pinfunction "Y_4") (pintype "bidirectional"))
    )
    (net (code "60") (name "PA_MATCH_OUT") (class "Default")
      (node (ref "C20") (pin "2") (pinfunction "2_2") (pintype "passive"))
      (node (ref "U8") (pin "4") (pinfunction "RF1_4") (pintype "bidirectional"))
    )
    (net (code "61") (name "PA_ON_LNA_OFF") (class "Default")
      (node (ref "R19") (pin "1") (pinfunction "1_1") (pintype "passive"))
      (node (ref "R21") (pin "2") (pinfunction "2_2") (pintype "passive"))
      (node (ref "U2") (pin "6") (pinfunction "OUT_6") (pintype "output"))
      (node (ref "U6") (pin "6") (pinfunction "IREF1_6") (pintype "bidirectional"))
    )
    (net (code "62") (name "PA_PAD_OUT") (class "Default")
      (node (ref "C24") (pin "1") (pinfunction "1_1") (pintype "passive"))
      (node (ref "R3") (pin "2") (pinfunction "2_2") (pintype "passive"))
      (node (ref "R4") (pin "1") (pinfunction "1_1") (pintype "passive"))
    )
    (net (code "63") (name "POST_LNA_FILTER_OUT") (class "Default")
      (node (ref "FL2") (pin "4") (pinfunction "OUT_4") (pintype "passive"))
      (node (ref "L8") (pin "2") (pinfunction "2_2") (pintype "bidirectional"))
      (node (ref "U4") (pin "4") (pinfunction "RF1_4") (pintype "bidirectional"))
    )
    (net (code "64") (name "PWR_DIV_OUT2") (class "Default")
      (node (ref "PD1") (pin "6") (pinfunction "OUT2_6") (pintype "output"))
      (node (ref "R39") (pin "2") (pinfunction "2_2") (pintype "passive"))
      (node (ref "U4") (pin "2") (pinfunction "RF_COM_2") (pintype "bidirectional"))
    )
    (net (code "65") (name "RX_IN") (class "Default")
      (node (ref "FL1") (pin "1") (pinfunction "IN_1") (pintype "passive"))
      (node (ref "L5") (pin "2") (pinfunction "2_2") (pintype "bidirectional"))
      (node (ref "U8") (pin "8") (pinfunction "RF2_8") (pintype "bidirectional"))
    )
    (net (code "66") (name "TX_RX_CTL") (class "Default")
      (node (ref "R26") (pin "1") (pinfunction "1_1") (pintype "passive"))
      (node (ref "U3") (pin "6") (pinfunction "OUT_6") (pintype "output"))
      (node (ref "U5") (pin "2") (pinfunction "A_2") (pintype "input"))
    )
  )
)
